# PT32S038x-Demo.net
KiCad netlist of a schematic drawn in EasyEDA Pro
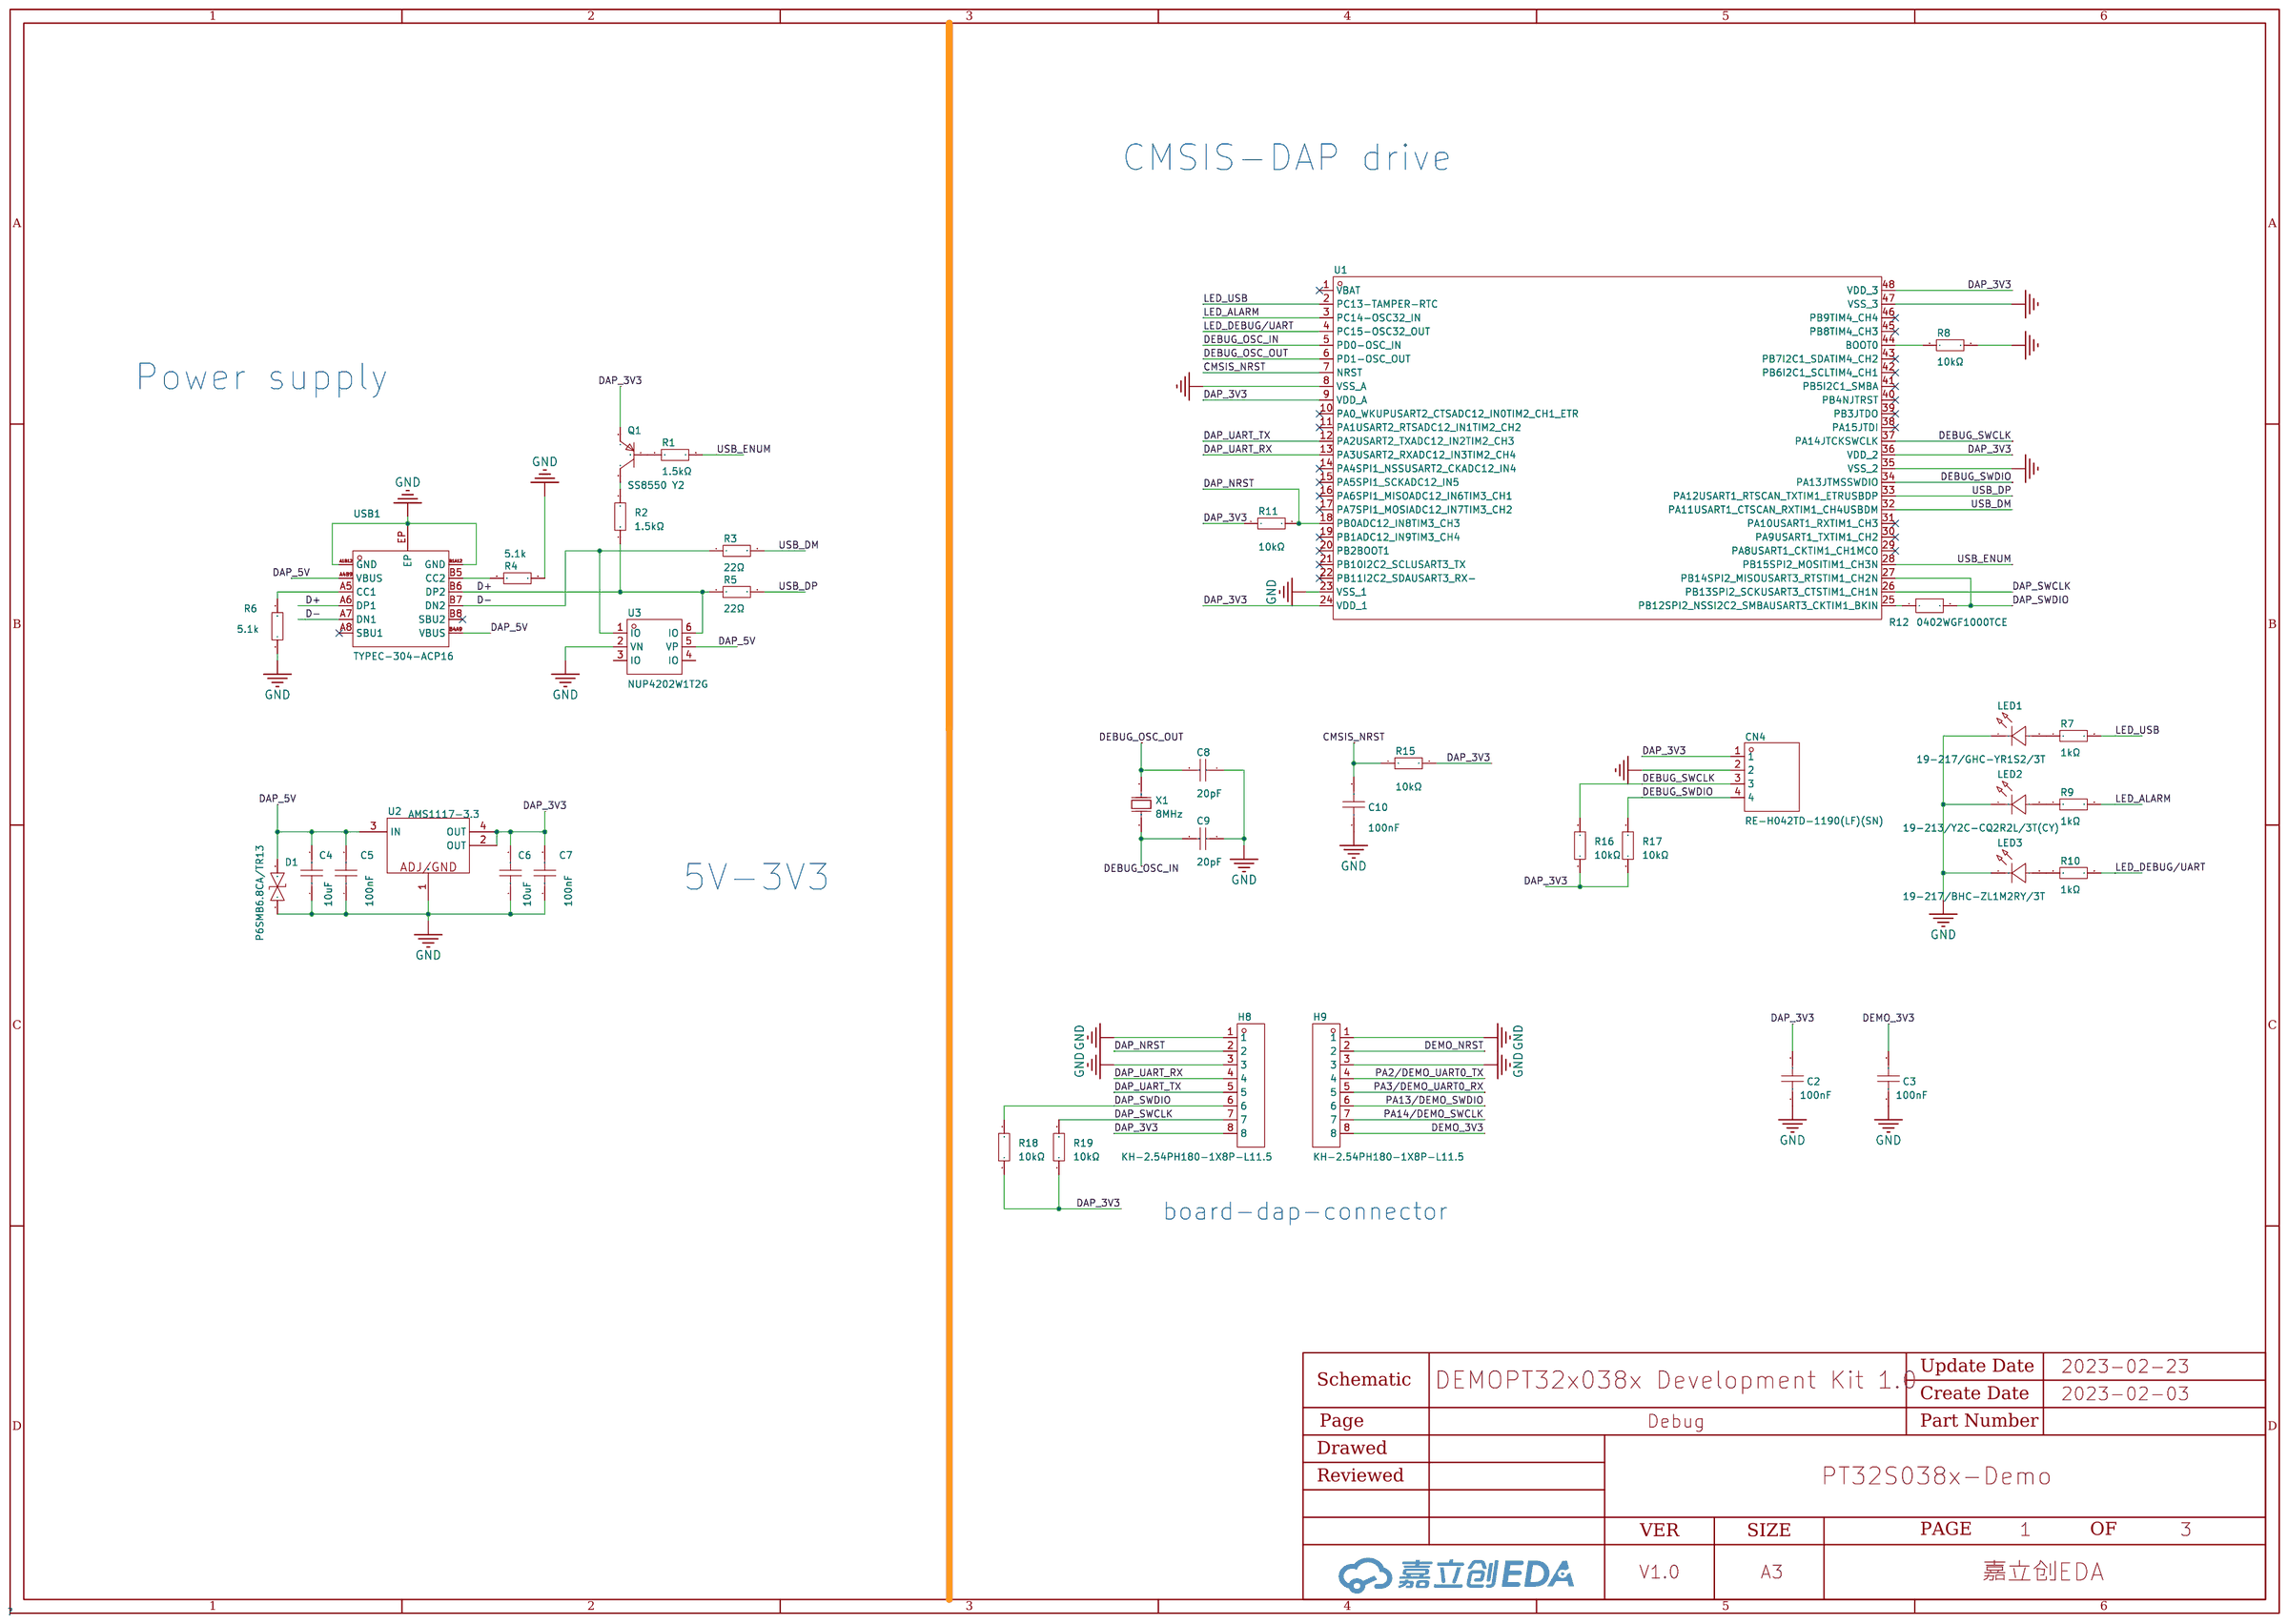
[diagram p0: Debug]
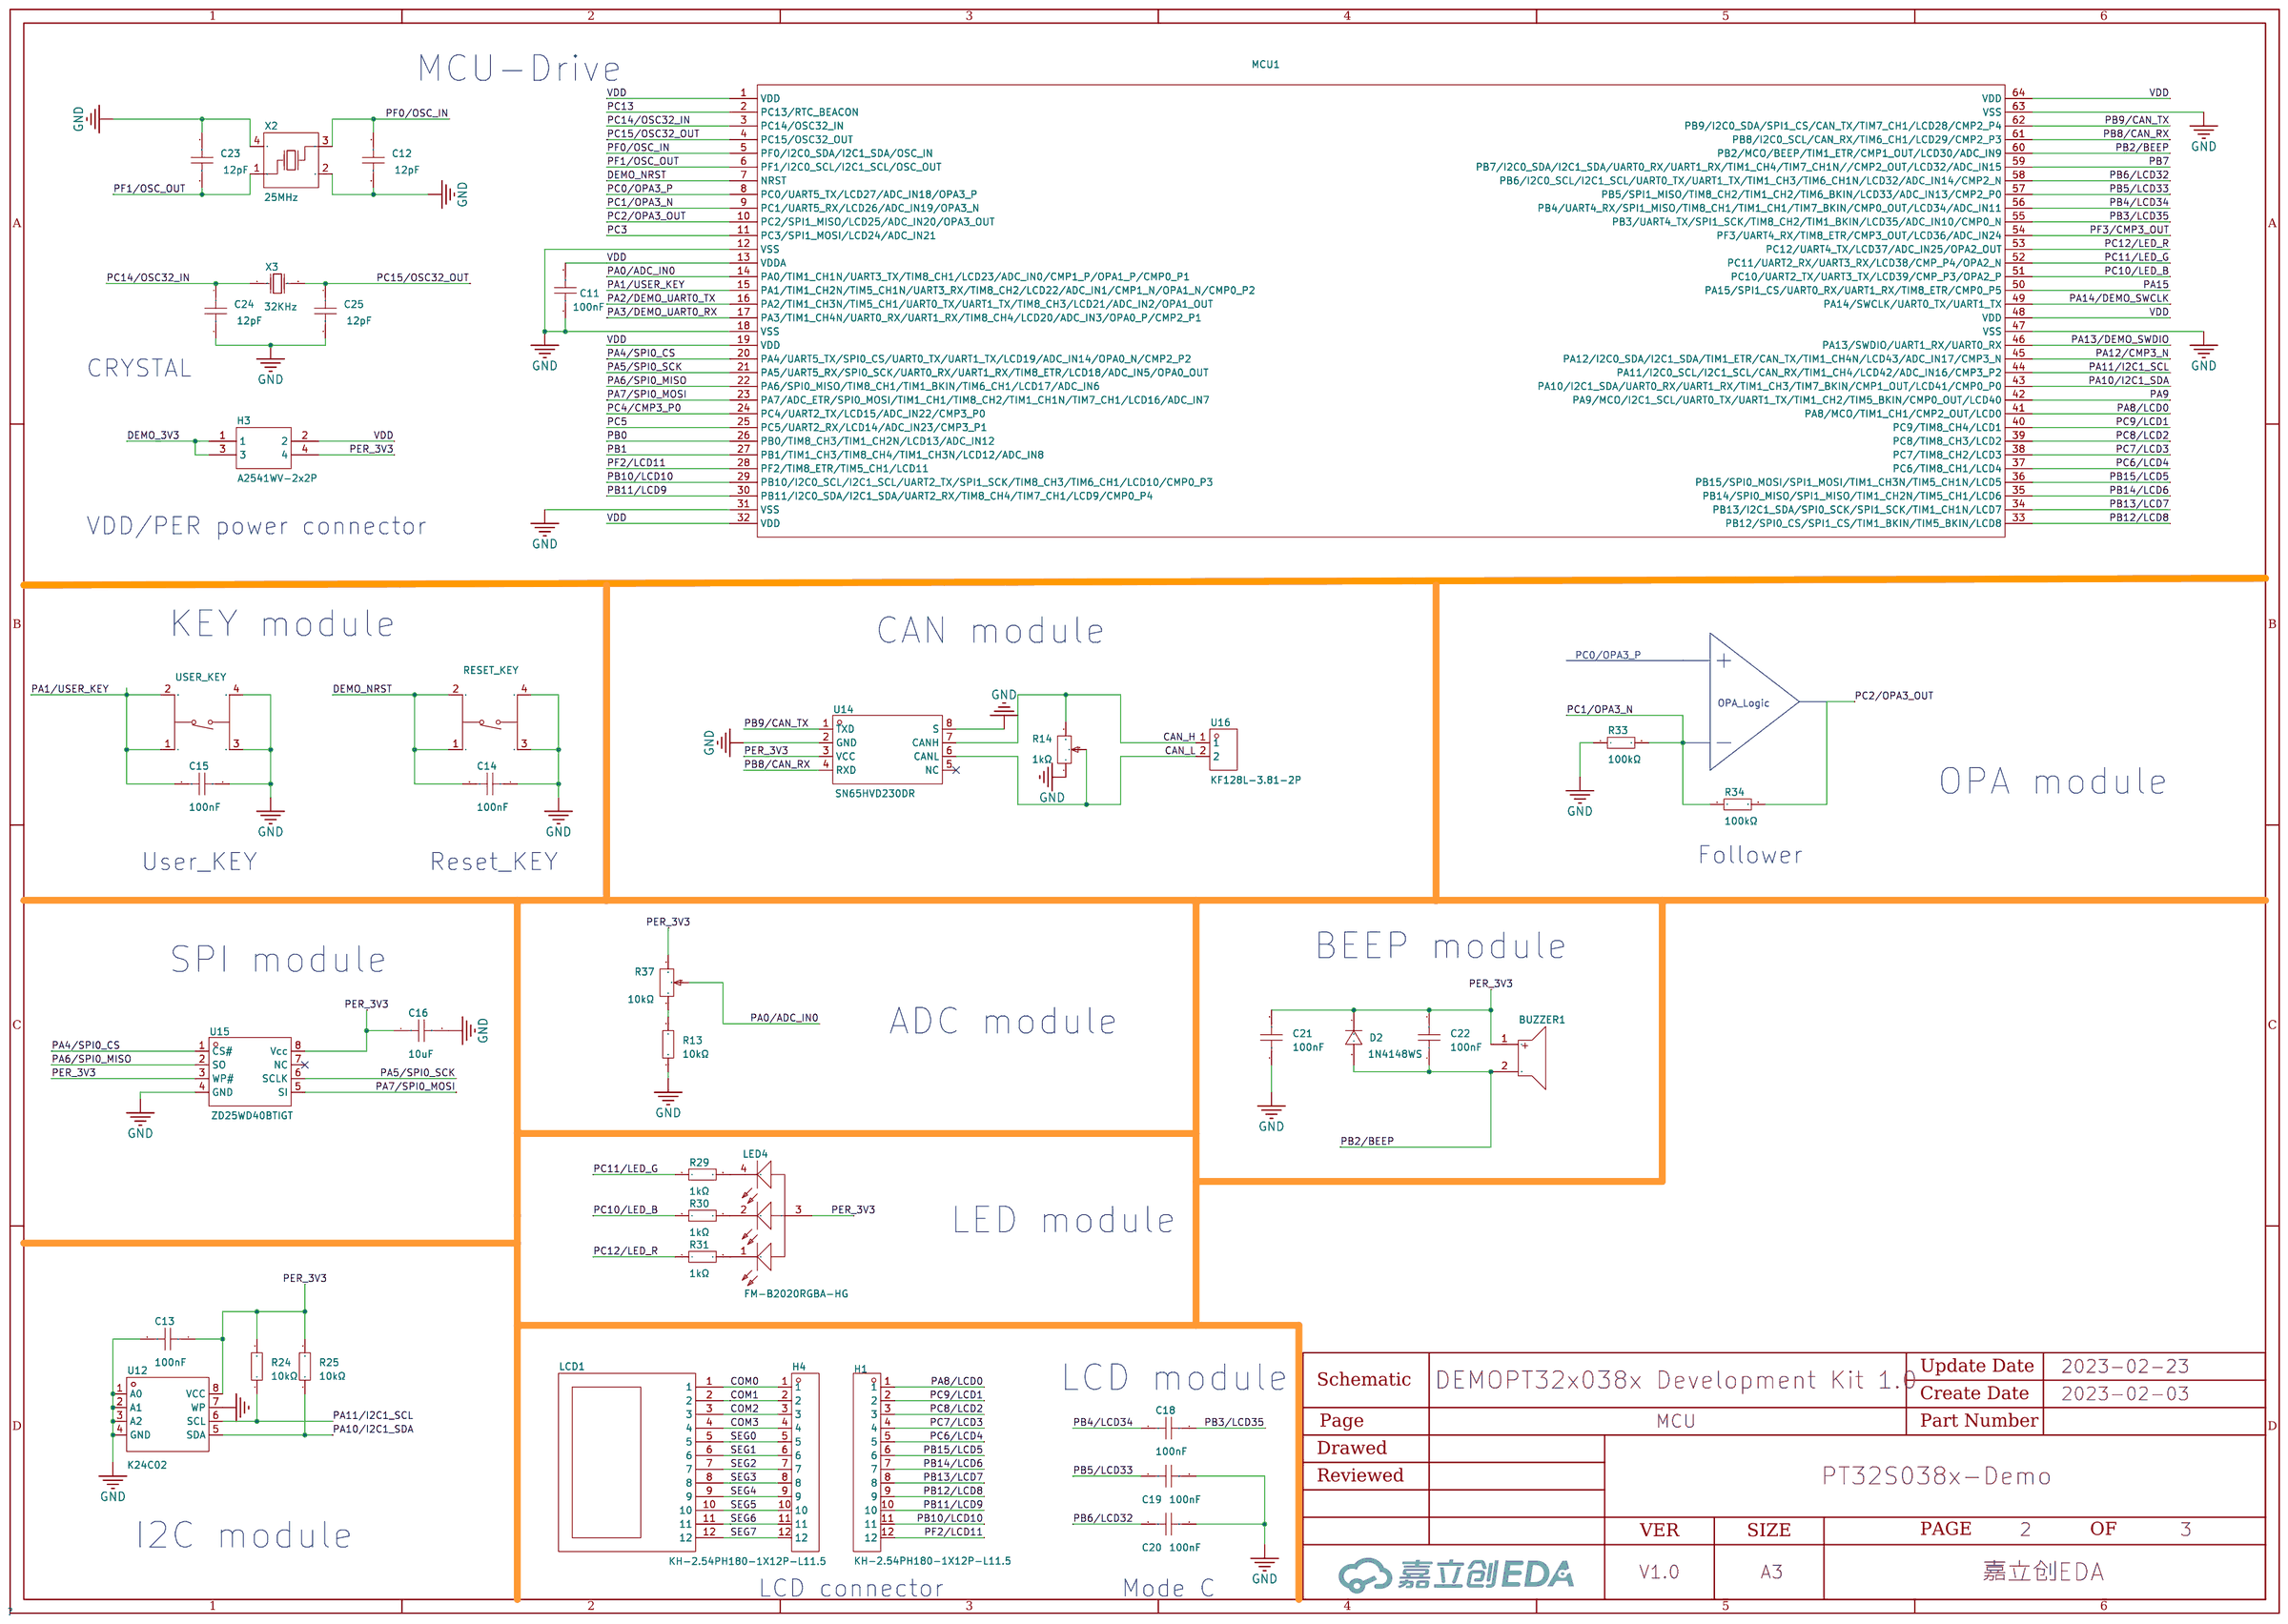
[diagram p1: MCU]
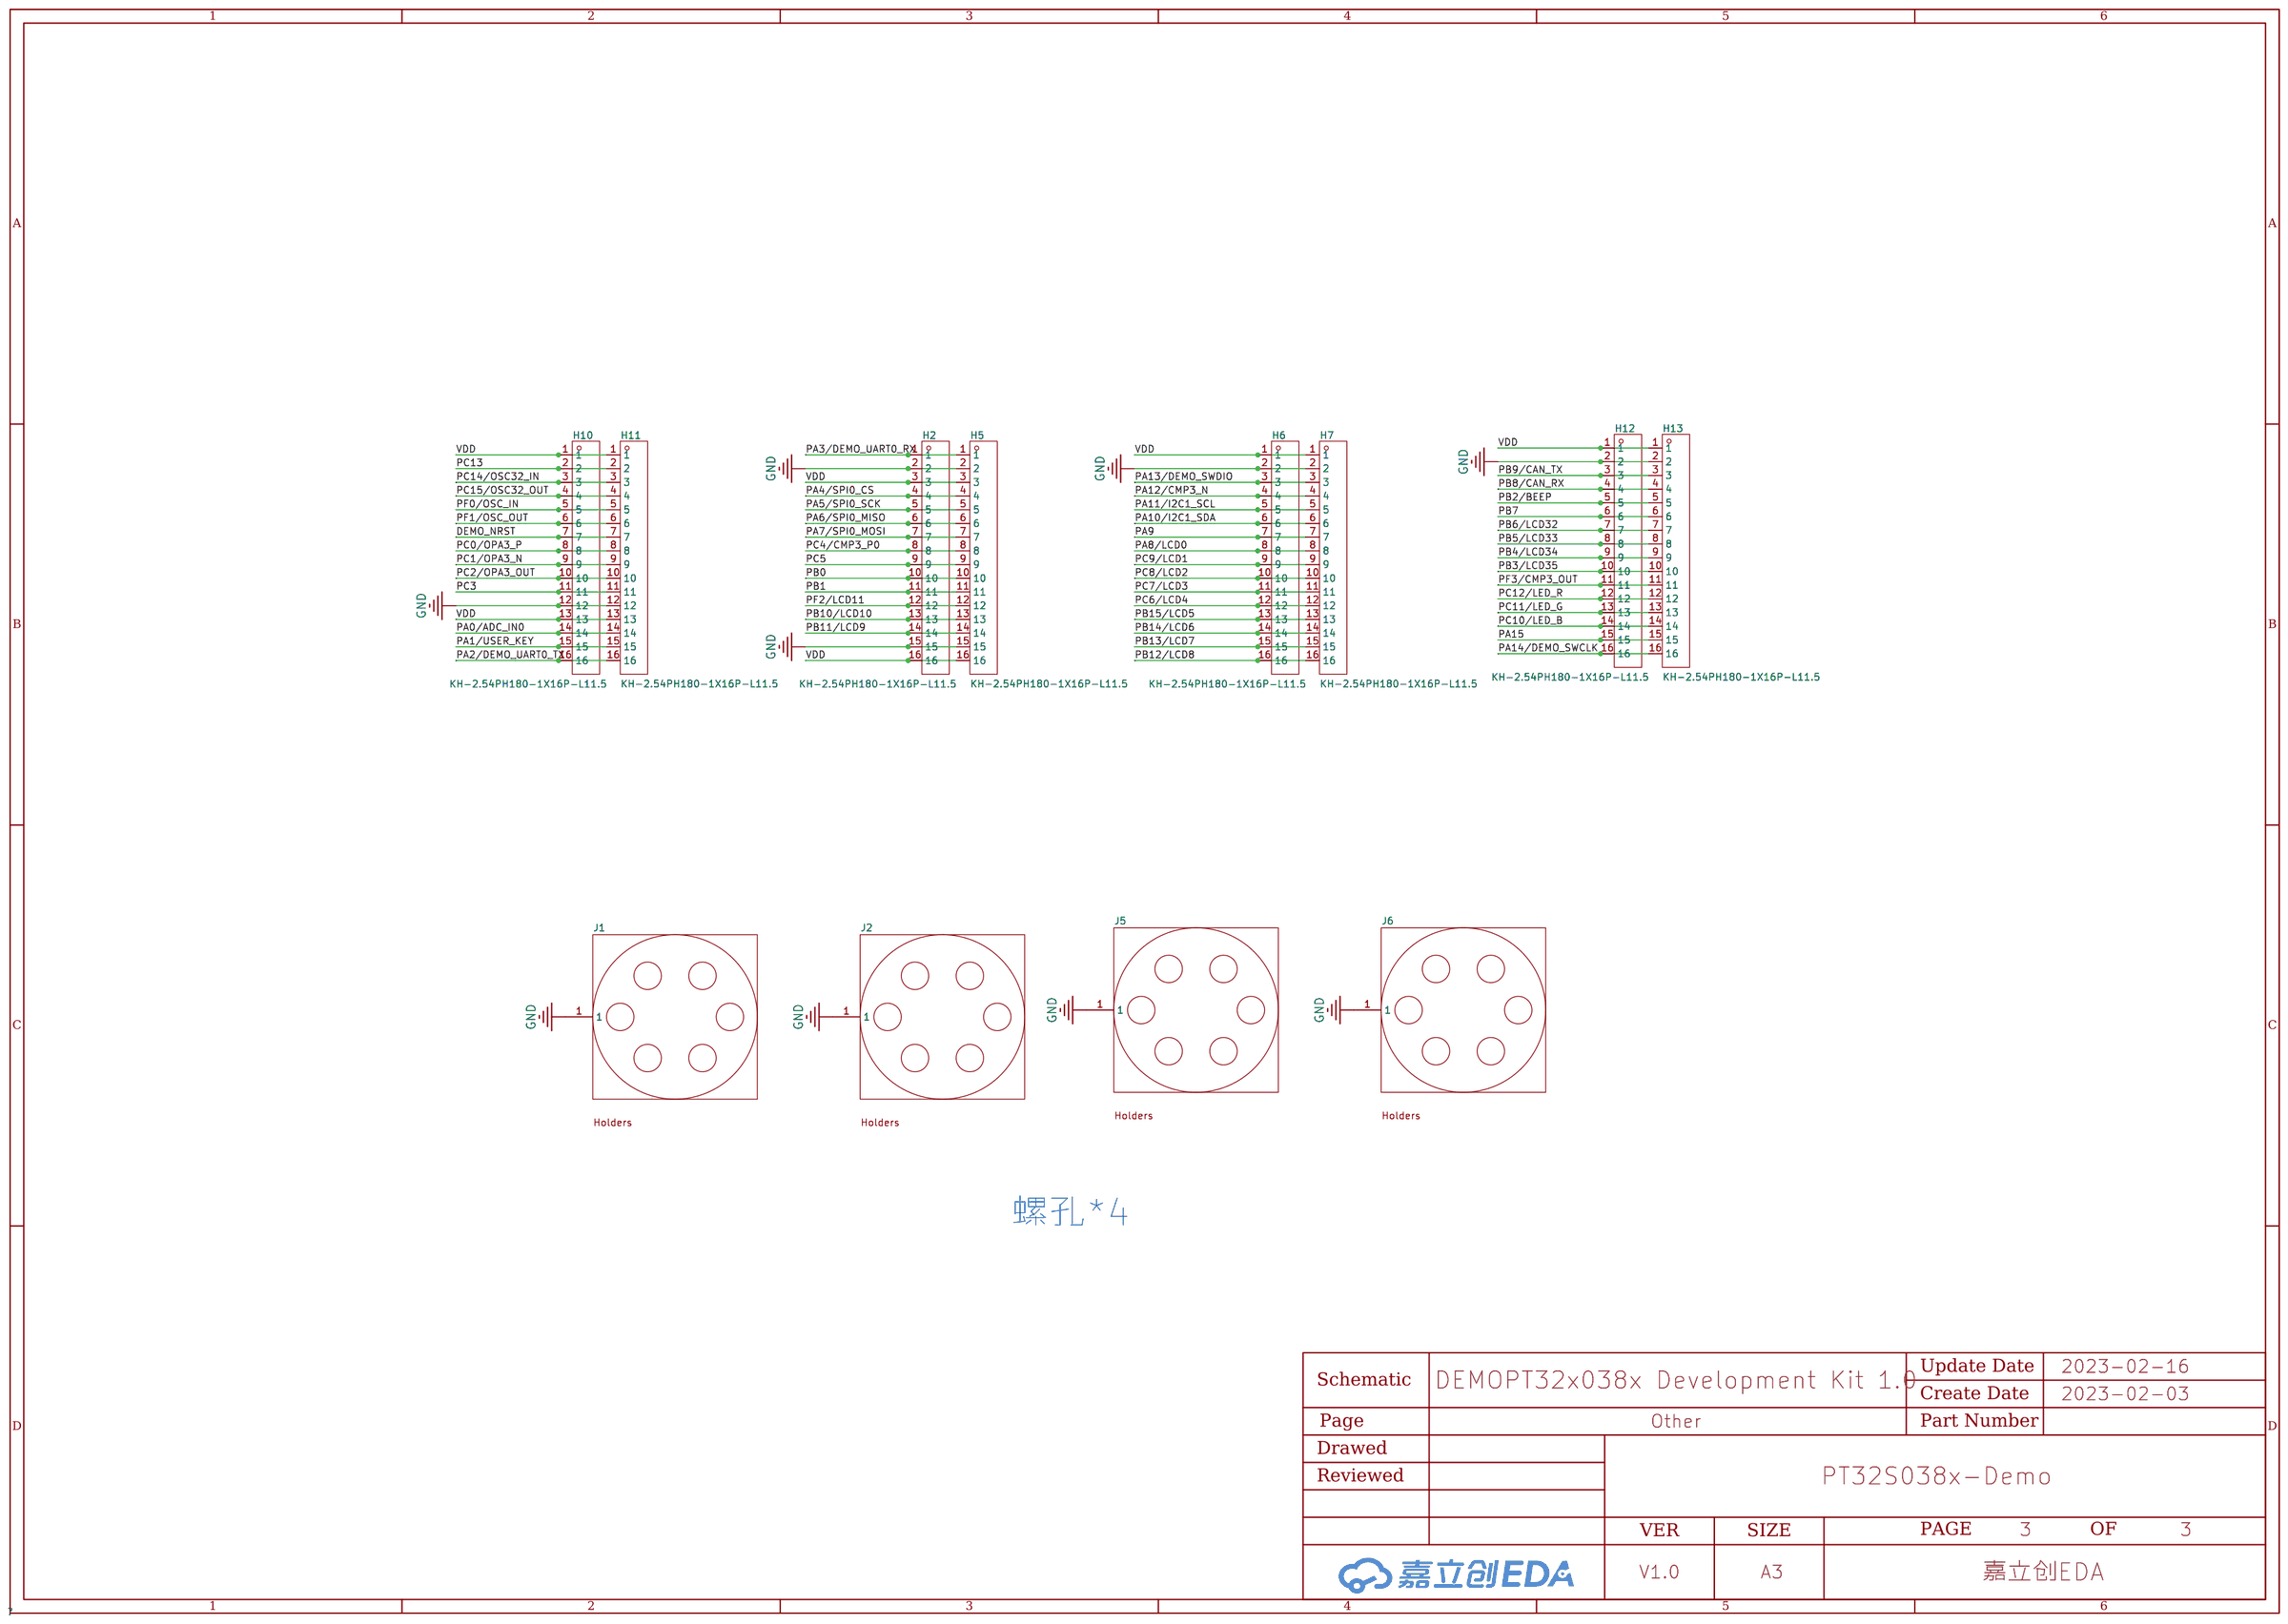
[diagram p2: Other]

(export (version "E")
  (design (tool "Eeschema 10.0.6"))
  (components
    (comp (ref "C2")
      (value "100nF")
      (footprint "easyedapro:C0603")
      (description "容值:100nF;精度:±10%;额定电压:50V;材质(温度系数):X7R;")
      (fields
        (field (name "Manufacturer Part") "CL05B104KB54PNC")
        (field (name "Manufacturer") "SAMSUNG(三星)")
      )
      (libsource (lib "easyedapro") (part "TCC0603X7R104K500CT"))
    )
    (comp (ref "C3")
      (value "100nF")
      (footprint "easyedapro:C0603")
      (description "容值:100nF;精度:±10%;额定电压:50V;材质(温度系数):X7R;")
      (fields
        (field (name "Manufacturer Part") "CL05B104KB54PNC")
        (field (name "Manufacturer") "SAMSUNG(三星)")
      )
      (libsource (lib "easyedapro") (part "TCC0603X7R104K500CT"))
    )
    (comp (ref "C4")
      (value "10uF")
      (footprint "easyedapro:C1210")
      (description "容值:10uF;精度:±10%;额定电压:50V;材质(温度系数):X7R;")
      (fields
        (field (name "Manufacturer Part") "CL31A106KBHNNNE")
        (field (name "Manufacturer") "SAMSUNG(三星)")
      )
      (libsource (lib "easyedapro") (part "C3225X7R1H106KT000E"))
    )
    (comp (ref "C5")
      (value "100nF")
      (footprint "easyedapro:C0603")
      (description "容值:100nF;精度:±10%;额定电压:50V;材质(温度系数):X7R;")
      (fields
        (field (name "Manufacturer Part") "CL05B104KB54PNC")
        (field (name "Manufacturer") "SAMSUNG(三星)")
      )
      (libsource (lib "easyedapro") (part "CC0603KRX7R9BB104"))
    )
    (comp (ref "C6")
      (value "10uF")
      (footprint "easyedapro:C1210")
      (description "容值:10uF;精度:±10%;额定电压:50V;材质(温度系数):X7R;")
      (fields
        (field (name "Manufacturer Part") "CL31A106KBHNNNE")
        (field (name "Manufacturer") "SAMSUNG(三星)")
      )
      (libsource (lib "easyedapro") (part "C3225X7R1H106KT000E"))
    )
    (comp (ref "C7")
      (value "100nF")
      (footprint "easyedapro:C0603")
      (description "容值:100nF;精度:±10%;额定电压:50V;材质(温度系数):X7R;")
      (fields
        (field (name "Manufacturer Part") "CL05B104KB54PNC")
        (field (name "Manufacturer") "SAMSUNG(三星)")
      )
      (libsource (lib "easyedapro") (part "CC0603KRX7R9BB104"))
    )
    (comp (ref "C8")
      (value "20pF")
      (footprint "easyedapro:C0603")
      (description "容值:20pF;精度:±5%;额定电压:50V;材质(温度系数):C0G;")
      (fields (field (name "Manufacturer Part") "0402CG200J500NT") (field (name "Manufacturer") "FH(风华)"))
      (libsource (lib "easyedapro") (part "GRM1885C1H200JA01D"))
    )
    (comp (ref "C9")
      (value "20pF")
      (footprint "easyedapro:C0603")
      (description "容值:20pF;精度:±5%;额定电压:50V;材质(温度系数):C0G;")
      (fields (field (name "Manufacturer Part") "0402CG200J500NT") (field (name "Manufacturer") "FH(风华)"))
      (libsource (lib "easyedapro") (part "GRM1885C1H200JA01D"))
    )
    (comp (ref "C10")
      (value "100nF")
      (footprint "easyedapro:C0603")
      (description "容值:100nF;精度:±10%;额定电压:50V;材质(温度系数):X7R;")
      (fields
        (field (name "Manufacturer Part") "CL05B104KB54PNC")
        (field (name "Manufacturer") "SAMSUNG(三星)")
      )
      (libsource (lib "easyedapro") (part "CC0603KRX7R9BB104"))
    )
    (comp (ref "CN4")
      (value "RE-H042TD-1190(LF)(SN)")
      (footprint "easyedapro:HDR-TH_4P-P2.54-V_RE-H042TD-1190")
      (fields (field (name "Manufacturer") "JST"))
      (libsource (lib "easyedapro") (part "RE-H042TD-1190 (LF)(SN)"))
    )
    (comp (ref "D1")
      (value "P6SMB6.8CA/TR13")
      (footprint "easyedapro:SMB_L4.6-W3.6-LS5.3-BI")
      (description "极性:双向;反向截止电压(Vrwm):5.8V;击穿电压(最小值):6.45V;峰值脉冲电流(Ipp)@10/1000s:58.1A;最大钳位电压:10.5V;")
      (fields (field (name "Manufacturer") "Brightking(君耀电子)"))
      (libsource (lib "easyedapro") (part "P6SMB6.8CA-C78395"))
    )
    (comp (ref "H8")
      (value "KH-2.54PH180-1X8P-L11.5")
      (footprint "easyedapro:HDR-TH_8P-P2.54-V-M")
      (fields (field (name "Manufacturer") "kinghelm(金航标)"))
      (libsource (lib "easyedapro") (part "KH-2.54PH180-1X8P-L11.5"))
    )
    (comp (ref "H9")
      (value "KH-2.54PH180-1X8P-L11.5")
      (footprint "easyedapro:HDR-TH_8P-P2.54-V-M")
      (fields (field (name "Manufacturer") "kinghelm(金航标)"))
      (libsource (lib "easyedapro") (part "KH-2.54PH180-1X8P-L11.5"))
    )
    (comp (ref "LED1")
      (value "19-217/GHC-YR1S2/3T")
      (footprint "easyedapro:LED0402-RD_GREEN")
      (fields (field (name "Manufacturer") "EVERLIGHT(亿光)"))
      (libsource (lib "easyedapro") (part "RF-GN0402TS-CF-B"))
    )
    (comp (ref "LED2")
      (value "19-213/Y2C-CQ2R2L/3T(CY)")
      (footprint "easyedapro:LED0402-RD_RED")
      (fields (field (name "Manufacturer") "EVERLIGHT(亿光)"))
      (libsource (lib "easyedapro") (part "RF-RU0402TS-BC-B1"))
    )
    (comp (ref "LED3")
      (value "19-217/BHC-ZL1M2RY/3T")
      (footprint "easyedapro:LED0402-RD_GREEN")
      (description "照明颜色:蓝色;主波长/色坐标:465~475nm;")
      (fields (field (name "Manufacturer") "EVERLIGHT(亿光)"))
      (libsource (lib "easyedapro") (part "RF-GN0402TS-CF-B"))
    )
    (comp (ref "Q1")
      (value "SS8550 Y2")
      (footprint "easyedapro:SOT-23-3_L2.9-W1.3-P1.90-LS2.4-BR")
      (fields (field (name "Manufacturer") "CJ(江苏长电/长晶)"))
      (libsource (lib "easyedapro") (part "SS8550_C8542"))
    )
    (comp (ref "R1")
      (value "1.5kΩ")
      (footprint "easyedapro:R0603")
      (description "阻值:1.5kΩ;精度:±1%;功率:1/16W;温度系数:±100ppm/℃;最大工作电压:50V;工作温度范围:-55℃~+155℃;")
      (fields
        (field (name "Manufacturer Part") "0402WGF1501TCE")
        (field (name "Manufacturer") "UNI-ROYAL(厚声)")
      )
      (libsource (lib "easyedapro") (part "0603WAF1501T5E"))
    )
    (comp (ref "R2")
      (value "1.5kΩ")
      (footprint "easyedapro:R0603")
      (description "阻值:1.5kΩ;精度:±1%;功率:1/16W;温度系数:±100ppm/℃;最大工作电压:50V;工作温度范围:-55℃~+155℃;")
      (fields
        (field (name "Manufacturer Part") "0402WGF1501TCE")
        (field (name "Manufacturer") "UNI-ROYAL(厚声)")
      )
      (libsource (lib "easyedapro") (part "0603WAF1501T5E"))
    )
    (comp (ref "R3")
      (value "22Ω")
      (footprint "easyedapro:R0402")
      (fields (field (name "Manufacturer") "UNI-ROYAL(厚声)"))
      (libsource (lib "easyedapro") (part "0402WGF220JTCE"))
    )
    (comp (ref "R4")
      (value "5.1kΩ")
      (footprint "easyedapro:R0603")
      (description "电阻类型:厚膜电阻;阻值:5.1kΩ;精度:±5%;功率:62.5mW;温度系数:±200ppm/℃;工作温度范围:-55℃~+155℃;")
      (fields (field (name "Manufacturer Part") "5.1k") (field (name "Manufacturer") "UNI-ROYAL(厚声)"))
      (libsource (lib "easyedapro") (part "RMC1/16-512JTP"))
    )
    (comp (ref "R5")
      (value "22Ω")
      (footprint "easyedapro:R0402")
      (fields (field (name "Manufacturer") "UNI-ROYAL(厚声)"))
      (libsource (lib "easyedapro") (part "0402WGF220JTCE"))
    )
    (comp (ref "R6")
      (value "5.1kΩ")
      (footprint "easyedapro:R0603")
      (description "电阻类型:厚膜电阻;阻值:5.1kΩ;精度:±5%;功率:62.5mW;温度系数:±200ppm/℃;工作温度范围:-55℃~+155℃;")
      (fields (field (name "Manufacturer Part") "5.1k") (field (name "Manufacturer") "UNI-ROYAL(厚声)"))
      (libsource (lib "easyedapro") (part "RMC1/16-512JTP"))
    )
    (comp (ref "R7")
      (value "1kΩ")
      (footprint "easyedapro:R0402")
      (description "电阻类型:厚膜电阻;阻值:1kΩ;精度:±1%;功率:62.5mW;温度系数:±100ppm/°C;最大工作电压:50V;工作温度范围:-55°C~+155°C;")
      (fields
        (field (name "Manufacturer Part") "0402WGF1001TCE")
        (field (name "Manufacturer") "UNI-ROYAL(厚声)")
      )
      (libsource (lib "easyedapro") (part "RC0402FR-071KL"))
    )
    (comp (ref "R8")
      (value "10kΩ")
      (footprint "easyedapro:R0603")
      (description "电阻类型:厚膜电阻;阻值:10kΩ;精度:±1%;功率:62.5mW;温度系数:±100ppm/℃;最大工作电压:50V;工作温度范围:-55℃~+155℃;")
      (fields
        (field (name "Manufacturer Part") "0402WGF1002TCE")
        (field (name "Manufacturer") "UNI-ROYAL(厚声)")
      )
      (libsource (lib "easyedapro") (part "RC0603JR-0710KL"))
    )
    (comp (ref "R9")
      (value "1kΩ")
      (footprint "easyedapro:R0402")
      (description "电阻类型:厚膜电阻;阻值:1kΩ;精度:±1%;功率:62.5mW;温度系数:±100ppm/°C;最大工作电压:50V;工作温度范围:-55°C~+155°C;")
      (fields
        (field (name "Manufacturer Part") "0402WGF1001TCE")
        (field (name "Manufacturer") "UNI-ROYAL(厚声)")
      )
      (libsource (lib "easyedapro") (part "RC0402FR-071KL"))
    )
    (comp (ref "R10")
      (value "1kΩ")
      (footprint "easyedapro:R0402")
      (description "电阻类型:厚膜电阻;阻值:1kΩ;精度:±1%;功率:62.5mW;温度系数:±100ppm/°C;最大工作电压:50V;工作温度范围:-55°C~+155°C;")
      (fields
        (field (name "Manufacturer Part") "0402WGF1001TCE")
        (field (name "Manufacturer") "UNI-ROYAL(厚声)")
      )
      (libsource (lib "easyedapro") (part "RC0402FR-071KL"))
    )
    (comp (ref "R11")
      (value "10kΩ")
      (footprint "easyedapro:R0603")
      (description "电阻类型:厚膜电阻;阻值:10kΩ;精度:±1%;功率:62.5mW;温度系数:±100ppm/℃;最大工作电压:50V;工作温度范围:-55℃~+155℃;")
      (fields
        (field (name "Manufacturer Part") "0402WGF1002TCE")
        (field (name "Manufacturer") "UNI-ROYAL(厚声)")
      )
      (libsource (lib "easyedapro") (part "RC0603JR-0710KL"))
    )
    (comp (ref "R12")
      (value "100Ω")
      (footprint "easyedapro:R0603")
      (description "电阻类型:厚膜电阻;阻值:100Ω;精度:±1%;功率:62.5mW;温度系数:±100ppm/℃;最大工作电压:50V;工作温度范围:-55℃~+155℃;")
      (fields
        (field (name "Manufacturer Part") "0402WGF1000TCE")
        (field (name "Manufacturer") "UNI-ROYAL(厚声)")
      )
      (libsource (lib "easyedapro") (part "0603 ±5% 100Ω"))
    )
    (comp (ref "R15")
      (value "10kΩ")
      (footprint "easyedapro:R0603")
      (description "电阻类型:厚膜电阻;阻值:10kΩ;精度:±1%;功率:62.5mW;温度系数:±100ppm/℃;最大工作电压:50V;工作温度范围:-55℃~+155℃;")
      (fields
        (field (name "Manufacturer Part") "0402WGF1002TCE")
        (field (name "Manufacturer") "UNI-ROYAL(厚声)")
      )
      (libsource (lib "easyedapro") (part "RC0603JR-0710KL"))
    )
    (comp (ref "R16")
      (value "10kΩ")
      (footprint "easyedapro:R0603")
      (description "电阻类型:厚膜电阻;阻值:10kΩ;精度:±1%;功率:62.5mW;温度系数:±100ppm/℃;最大工作电压:50V;工作温度范围:-55℃~+155℃;")
      (fields
        (field (name "Manufacturer Part") "0402WGF1002TCE")
        (field (name "Manufacturer") "UNI-ROYAL(厚声)")
      )
      (libsource (lib "easyedapro") (part "RC0603JR-0710KL"))
    )
    (comp (ref "R17")
      (value "10kΩ")
      (footprint "easyedapro:R0603")
      (description "电阻类型:厚膜电阻;阻值:10kΩ;精度:±1%;功率:62.5mW;温度系数:±100ppm/℃;最大工作电压:50V;工作温度范围:-55℃~+155℃;")
      (fields
        (field (name "Manufacturer Part") "0402WGF1002TCE")
        (field (name "Manufacturer") "UNI-ROYAL(厚声)")
      )
      (libsource (lib "easyedapro") (part "RC0603JR-0710KL"))
    )
    (comp (ref "R18")
      (value "10kΩ")
      (footprint "easyedapro:R0603")
      (description "电阻类型:厚膜电阻;阻值:10kΩ;精度:±1%;功率:62.5mW;温度系数:±100ppm/℃;最大工作电压:50V;工作温度范围:-55℃~+155℃;")
      (fields
        (field (name "Manufacturer Part") "0402WGF1002TCE")
        (field (name "Manufacturer") "UNI-ROYAL(厚声)")
      )
      (libsource (lib "easyedapro") (part "RC0603JR-0710KL"))
    )
    (comp (ref "R19")
      (value "10kΩ")
      (footprint "easyedapro:R0603")
      (description "电阻类型:厚膜电阻;阻值:10kΩ;精度:±1%;功率:62.5mW;温度系数:±100ppm/℃;最大工作电压:50V;工作温度范围:-55℃~+155℃;")
      (fields
        (field (name "Manufacturer Part") "0402WGF1002TCE")
        (field (name "Manufacturer") "UNI-ROYAL(厚声)")
      )
      (libsource (lib "easyedapro") (part "RC0603JR-0710KL"))
    )
    (comp (ref "U1")
      (value "STM32F103CBT6")
      (footprint "easyedapro:LQFP-48_L7.0-W7.0-P0.50-LS9.0-BL")
      (description "主频（MAX):72MHz;工作电压:2V ~ 3.6V;")
      (fields (field (name "Manufacturer") "ST(意法半导体)"))
      (libsource (lib "easyedapro") (part "STM32F103CBT6"))
    )
    (comp (ref "U2")
      (value "AMS1117-3.3")
      (footprint "easyedapro:SOT-223-3_L6.4-W3.5-P2.30-LS7.0-BR")
      (fields (field (name "Manufacturer") "AMS"))
      (libsource (lib "easyedapro") (part "AMS1117-3.3_C2992570"))
    )
    (comp (ref "U3")
      (value "NUP4202W1T2G")
      (footprint "easyedapro:SOT-363_L2.0-W1.3-P0.65-LS2.1-BR")
      (fields (field (name "Manufacturer") "onsemi(安森美)"))
      (libsource (lib "easyedapro") (part "NUP4202W1T2G"))
    )
    (comp (ref "USB1")
      (value "TYPEC-304-ACP16")
      (footprint "easyedapro:USB-C-SMD_TYPE-C-16P-1")
      (description "连接器类型:-;标准:-;公母:-;触点数量:-;端口数量:-;安装方式:-;额定电流 - 电源:-;触头材质:-;触头镀层:-;工作温度范围:-;")
      (fields (field (name "Manufacturer") "XUNPU(讯普)"))
      (libsource (lib "easyedapro") (part "TYPEC-304-ACP16"))
    )
    (comp (ref "X1")
      (value "8MHz")
      (footprint "easyedapro:CRYSTAL-SMD_L5.0-W3.2")
      (description "晶振类型:贴片无源晶振;频率:8MHz;频率公差:±10ppm;频率稳定度:±50ppm;负载电容:20pF;工作温度:-40℃~+85℃;")
      (fields (field (name "Manufacturer Part") "X50328MSB2GI") (field (name "Manufacturer") "YXC(扬兴晶振)"))
      (libsource (lib "easyedapro") (part "ECS-80-8-30Q-VY-TR"))
    )
    (comp (ref "BUZZER1")
      (value "2700Hz")
      (footprint "easyedapro:BUZ-TH_BD9.0-P4.00-D0.6-FD")
      (description "驱动方式:无源(外部驱动);构造类型:电磁式;额定电压:3V;工作电压:2V~5V;频率:2700Hz;声压(SPL):85dB@3V,10cm;直径(φD):9mm;高度:5.7mm;")
      (fields (field (name "Manufacturer Part") "FS9042-03") (field (name "Manufacturer") "FUET(福声科技)"))
      (libsource (lib "easyedapro") (part "QMB-09B-03"))
    )
    (comp (ref "C11")
      (value "100nF")
      (footprint "easyedapro:C0603")
      (description "容值:100nF;精度:±10%;额定电压:50V;材质(温度系数):X7R;")
      (fields
        (field (name "Manufacturer Part") "CL05B104KB54PNC")
        (field (name "Manufacturer") "SAMSUNG(三星)")
      )
      (libsource (lib "easyedapro") (part "TCC0603X7R104K500CT"))
    )
    (comp (ref "C12")
      (value "12pF")
      (footprint "easyedapro:C0402")
      (description "容值:12pF;精度:±5%;额定电压:50V;材质(温度系数):C0G;")
      (fields (field (name "Manufacturer Part") "0402CG120J500NT") (field (name "Manufacturer") "FH(风华)"))
      (libsource (lib "easyedapro") (part "GJM1555C1H120GB01D"))
    )
    (comp (ref "C13")
      (value "100nF")
      (footprint "easyedapro:C0603")
      (description "容值:100nF;精度:±10%;额定电压:50V;材质(温度系数):X7R;")
      (fields
        (field (name "Manufacturer Part") "CL05B104KB54PNC")
        (field (name "Manufacturer") "SAMSUNG(三星)")
      )
      (libsource (lib "easyedapro") (part "TCC0603X7R104K500CT"))
    )
    (comp (ref "C14")
      (value "100nF")
      (footprint "easyedapro:C0603")
      (description "容值:100nF;精度:±10%;额定电压:50V;材质(温度系数):X7R;")
      (fields
        (field (name "Manufacturer Part") "CL05B104KB54PNC")
        (field (name "Manufacturer") "SAMSUNG(三星)")
      )
      (libsource (lib "easyedapro") (part "TCC0603X7R104K500CT"))
    )
    (comp (ref "C15")
      (value "100nF")
      (footprint "easyedapro:C0603")
      (description "容值:100nF;精度:±10%;额定电压:50V;材质(温度系数):X7R;")
      (fields
        (field (name "Manufacturer Part") "CL05B104KB54PNC")
        (field (name "Manufacturer") "SAMSUNG(三星)")
      )
      (libsource (lib "easyedapro") (part "TCC0603X7R104K500CT"))
    )
    (comp (ref "C16")
      (value "10uF")
      (footprint "easyedapro:C0402")
      (description "容值:10uF;精度:±20%;额定电压:10V;材质(温度系数):X5R;")
      (fields
        (field (name "Manufacturer Part") "CL05A106MQ5NUNC")
        (field (name "Manufacturer") "SAMSUNG(三星)")
      )
      (libsource (lib "easyedapro") (part "CL05A106MP5NUNC_C315248"))
    )
    (comp (ref "C18")
      (value "100nF")
      (footprint "easyedapro:C0603")
      (description "容值:100nF;精度:±10%;额定电压:50V;材质(温度系数):X7R;")
      (fields
        (field (name "Manufacturer Part") "CL05B104KB54PNC")
        (field (name "Manufacturer") "SAMSUNG(三星)")
      )
      (libsource (lib "easyedapro") (part "TCC0603X7R104K500CT"))
    )
    (comp (ref "C19")
      (value "100nF")
      (footprint "easyedapro:C0603")
      (description "容值:100nF;精度:±10%;额定电压:50V;材质(温度系数):X7R;")
      (fields
        (field (name "Manufacturer Part") "CL05B104KB54PNC")
        (field (name "Manufacturer") "SAMSUNG(三星)")
      )
      (libsource (lib "easyedapro") (part "TCC0603X7R104K500CT"))
    )
    (comp (ref "C20")
      (value "100nF")
      (footprint "easyedapro:C0603")
      (description "容值:100nF;精度:±10%;额定电压:50V;材质(温度系数):X7R;")
      (fields
        (field (name "Manufacturer Part") "CL05B104KB54PNC")
        (field (name "Manufacturer") "SAMSUNG(三星)")
      )
      (libsource (lib "easyedapro") (part "TCC0603X7R104K500CT"))
    )
    (comp (ref "C21")
      (value "100nF")
      (footprint "easyedapro:C0603")
      (description "容值:100nF;精度:±10%;额定电压:50V;材质(温度系数):X7R;")
      (fields
        (field (name "Manufacturer Part") "CL05B104KB54PNC")
        (field (name "Manufacturer") "SAMSUNG(三星)")
      )
      (libsource (lib "easyedapro") (part "TCC0603X7R104K500CT"))
    )
    (comp (ref "C22")
      (value "100nF")
      (footprint "easyedapro:C0603")
      (description "容值:100nF;精度:±10%;额定电压:50V;材质(温度系数):X7R;")
      (fields
        (field (name "Manufacturer Part") "CL05B104KB54PNC")
        (field (name "Manufacturer") "SAMSUNG(三星)")
      )
      (libsource (lib "easyedapro") (part "TCC0603X7R104K500CT"))
    )
    (comp (ref "C23")
      (value "12pF")
      (footprint "easyedapro:C0402")
      (description "容值:12pF;精度:±5%;额定电压:50V;材质(温度系数):C0G;")
      (fields (field (name "Manufacturer Part") "0402CG120J500NT") (field (name "Manufacturer") "FH(风华)"))
      (libsource (lib "easyedapro") (part "GJM1555C1H120GB01D"))
    )
    (comp (ref "C24")
      (value "12pF")
      (footprint "easyedapro:C0402")
      (description "容值:12pF;精度:±5%;额定电压:50V;材质(温度系数):C0G;")
      (fields (field (name "Manufacturer Part") "0402CG120J500NT") (field (name "Manufacturer") "FH(风华)"))
      (libsource (lib "easyedapro") (part "GJM1555C1H120GB01D"))
    )
    (comp (ref "C25")
      (value "12pF")
      (footprint "easyedapro:C0402")
      (description "容值:12pF;精度:±5%;额定电压:50V;材质(温度系数):C0G;")
      (fields (field (name "Manufacturer Part") "0402CG120J500NT") (field (name "Manufacturer") "FH(风华)"))
      (libsource (lib "easyedapro") (part "GJM1555C1H120GB01D"))
    )
    (comp (ref "D2")
      (value "1N4148WS")
      (footprint "easyedapro:SOD-323_L1.8-W1.3-LS2.5-RD")
      (fields (field (name "Manufacturer") "CJ(江苏长电/长晶)"))
      (libsource (lib "easyedapro") (part "IN4148WS"))
    )
    (comp (ref "H1")
      (value "KH-2.54PH180-1X12P-L11.5")
      (footprint "easyedapro:HDR-TH_12P-P2.54-V-M")
      (fields (field (name "Manufacturer") "kinghelm(金航标)"))
      (libsource (lib "easyedapro") (part "KH-2.54PH180-1X12P-L11.5"))
    )
    (comp (ref "H3")
      (value "A2541WV-2x2P")
      (footprint "easyedapro:HDR-TH_4P-P2.54-V-R2-C2-S2.54_A2541WV-2X2P")
      (fields (field (name "Manufacturer") "CJT(长江连接器)"))
      (libsource (lib "easyedapro") (part "A2541WV-2X2P"))
    )
    (comp (ref "H4")
      (value "KH-2.54PH180-1X12P-L11.5")
      (footprint "easyedapro:HDR-TH_12P-P2.54-V-M")
      (fields (field (name "Manufacturer") "kinghelm(金航标)"))
      (libsource (lib "easyedapro") (part "KH-2.54PH180-1X12P-L11.5"))
    )
    (comp (ref "LCD1")
      (value "~")
      (footprint "easyedapro:LCD_12pin_4com_8seg")
      (description "LCD screen with 4COM and 8SEG")
      (libsource (lib "easyedapro") (part "LCD_12pin_4com_8seg"))
    )
    (comp (ref "LED4")
      (value "FM-B2020RGBA-HG")
      (footprint "easyedapro:LED-SMD_FM-B2020RGBA-HG")
      (description "发光颜色:RGB三色;")
      (fields (field (name "Manufacturer") "国星光电"))
      (libsource (lib "easyedapro") (part "FM-B2020RGBA-HG"))
    )
    (comp (ref "MCU1")
      (value "~")
      (description "PengPai-Microelectronics Micro control uint")
      (libsource (lib "easyedapro") (part "PT32S038x"))
    )
    (comp (ref "R13")
      (value "10kΩ")
      (footprint "easyedapro:R0603")
      (description "电阻类型:厚膜电阻;阻值:10kΩ;精度:±1%;功率:62.5mW;温度系数:±100ppm/℃;最大工作电压:50V;工作温度范围:-55℃~+155℃;")
      (fields
        (field (name "Manufacturer Part") "0402WGF1002TCE")
        (field (name "Manufacturer") "UNI-ROYAL(厚声)")
      )
      (libsource (lib "easyedapro") (part "RC0603JR-0710KL"))
    )
    (comp (ref "R14")
      (value "1kΩ")
      (footprint "easyedapro:RES-ADJ-TH_3362P")
      (description "阻值:1kΩ;精度:±10%;")
      (fields (field (name "Manufacturer Part") "3362P-1-102LF") (field (name "Manufacturer") "BOURNS"))
      (libsource (lib "easyedapro") (part "3362P-1-102LF"))
    )
    (comp (ref "R24")
      (value "10kΩ")
      (footprint "easyedapro:R0603")
      (description "电阻类型:厚膜电阻;阻值:10kΩ;精度:±1%;功率:62.5mW;温度系数:±100ppm/℃;最大工作电压:50V;工作温度范围:-55℃~+155℃;")
      (fields
        (field (name "Manufacturer Part") "0402WGF1002TCE")
        (field (name "Manufacturer") "UNI-ROYAL(厚声)")
      )
      (libsource (lib "easyedapro") (part "RC0603JR-0710KL"))
    )
    (comp (ref "R25")
      (value "10kΩ")
      (footprint "easyedapro:R0603")
      (description "电阻类型:厚膜电阻;阻值:10kΩ;精度:±1%;功率:62.5mW;温度系数:±100ppm/℃;最大工作电压:50V;工作温度范围:-55℃~+155℃;")
      (fields
        (field (name "Manufacturer Part") "0402WGF1002TCE")
        (field (name "Manufacturer") "UNI-ROYAL(厚声)")
      )
      (libsource (lib "easyedapro") (part "RC0603JR-0710KL"))
    )
    (comp (ref "R29")
      (value "1kΩ")
      (footprint "easyedapro:R0402")
      (description "电阻类型:厚膜电阻;阻值:1kΩ;精度:±1%;功率:62.5mW;温度系数:±100ppm/°C;最大工作电压:50V;工作温度范围:-55°C~+155°C;")
      (fields
        (field (name "Manufacturer Part") "0402WGF1001TCE")
        (field (name "Manufacturer") "UNI-ROYAL(厚声)")
      )
      (libsource (lib "easyedapro") (part "RC0402FR-071KL"))
    )
    (comp (ref "R30")
      (value "1kΩ")
      (footprint "easyedapro:R0402")
      (description "电阻类型:厚膜电阻;阻值:1kΩ;精度:±1%;功率:62.5mW;温度系数:±100ppm/°C;最大工作电压:50V;工作温度范围:-55°C~+155°C;")
      (fields
        (field (name "Manufacturer Part") "0402WGF1001TCE")
        (field (name "Manufacturer") "UNI-ROYAL(厚声)")
      )
      (libsource (lib "easyedapro") (part "RC0402FR-071KL"))
    )
    (comp (ref "R31")
      (value "1kΩ")
      (footprint "easyedapro:R0402")
      (description "电阻类型:厚膜电阻;阻值:1kΩ;精度:±1%;功率:62.5mW;温度系数:±100ppm/°C;最大工作电压:50V;工作温度范围:-55°C~+155°C;")
      (fields
        (field (name "Manufacturer Part") "0402WGF1001TCE")
        (field (name "Manufacturer") "UNI-ROYAL(厚声)")
      )
      (libsource (lib "easyedapro") (part "RC0402FR-071KL"))
    )
    (comp (ref "R33")
      (value "100kΩ")
      (footprint "easyedapro:R0402")
      (description "电阻类型:厚膜电阻;阻值:100kΩ;精度:±1%;功率:62.5mW;温度系数:±100ppm/°C;最大工作电压:50V;工作温度范围:-55°C~+155°C;")
      (fields
        (field (name "Manufacturer Part") "0402WGF1003TCE")
        (field (name "Manufacturer") "UNI-ROYAL(厚声)")
      )
      (libsource (lib "easyedapro") (part "0402WGF1003TCE"))
    )
    (comp (ref "R34")
      (value "100kΩ")
      (footprint "easyedapro:R0402")
      (description "电阻类型:厚膜电阻;阻值:100kΩ;精度:±1%;功率:62.5mW;温度系数:±100ppm/°C;最大工作电压:50V;工作温度范围:-55°C~+155°C;")
      (fields
        (field (name "Manufacturer Part") "0402WGF1003TCE")
        (field (name "Manufacturer") "UNI-ROYAL(厚声)")
      )
      (libsource (lib "easyedapro") (part "0402WGF1003TCE"))
    )
    (comp (ref "R37")
      (value "10kΩ")
      (footprint "easyedapro:RES-ADJ-TH_3362P")
      (description "阻值:10kΩ;精度:±10%;")
      (fields (field (name "Manufacturer Part") "3362P-1-103LF") (field (name "Manufacturer") "BOURNS"))
      (libsource (lib "easyedapro") (part "3362P-1-102LF"))
    )
    (comp (ref "RESET_KEY")
      (value "TS-1187A-B-A-B")
      (footprint "easyedapro:SW-SMD_4P-L5.1-W5.1-P3.70-LS6.5-TL-2")
      (description "触点电流:20mA;额定电压(DC):12V;电路结构:单刀单掷;安装方式:立贴;按钮形状:圆形按钮;带灯:-;开关长度:5.1mm;开关宽度:5.1mm;开关高度:0.3mm;")
      (fields (field (name "Manufacturer") "XKB Connectivity(中国星坤)"))
      (libsource (lib "easyedapro") (part "1TS001G-2500-1500"))
    )
    (comp (ref "U12")
      (value "K24C02")
      (footprint "easyedapro:SOIC-8_L4.9-W3.9-P1.27-LS6.0-BL")
      (description "2-Kbit(256 x 8bit)，I2C接口，工作电压：1.7V to 5.5V")
      (fields (field (name "Manufacturer") "华虹宏力"))
      (libsource (lib "easyedapro") (part "K24C02_C10510"))
    )
    (comp (ref "U14")
      (value "SN65HVD230DR")
      (footprint "easyedapro:SOIC-8_L4.9-W3.9-P1.27-LS6.0-BL")
      (description "类型:收发器;数据速率:5Mbps;电源电压(Vcc):4.5V~5.5V;")
      (fields (field (name "Manufacturer") "TI(德州仪器)"))
      (libsource (lib "easyedapro") (part "TJA1051T/1J"))
    )
    (comp (ref "U15")
      (value "ZD25WD40BTIGT")
      (footprint "easyedapro:SOIC-8_L4.9-W3.9-P1.27-LS6.0-BL")
      (description "SPI NOR Flash，4Mb，2.3-3.6V，SOP8-150，Tube")
      (fields (field (name "Manufacturer") "Zetta(澜智)"))
      (libsource (lib "easyedapro") (part "ZD25WD40BTIGT"))
    )
    (comp (ref "U16")
      (value "KF128L-3.81-2P")
      (footprint "easyedapro:CONN-TH_P3.81_KF128L-3.81-2P")
      (fields (field (name "Manufacturer") "KEFA(科发)"))
      (libsource (lib "easyedapro") (part "KF128L-3.81-2P"))
    )
    (comp (ref "USER_KEY")
      (value "TS-1187A-B-A-B")
      (footprint "easyedapro:SW-SMD_4P-L5.1-W5.1-P3.70-LS6.5-TL-2")
      (description "触点电流:20mA;额定电压(DC):12V;电路结构:单刀单掷;安装方式:立贴;按钮形状:圆形按钮;带灯:-;开关长度:5.1mm;开关宽度:5.1mm;开关高度:0.3mm;")
      (fields (field (name "Manufacturer") "XKB Connectivity(中国星坤)"))
      (libsource (lib "easyedapro") (part "1TS001G-2500-1500"))
    )
    (comp (ref "X2")
      (value "25MHz")
      (footprint "easyedapro:OSC-SMD_4P-L3.2-W2.5-BL")
      (description "晶振类型:贴片无源晶振;频率:25MHz;频率公差:±10ppm;频率稳定度:±30ppm;负载电容:12pF;工作温度:-40~+85;")
      (fields (field (name "Manufacturer Part") "X322525MOB4SI") (field (name "Manufacturer") "YXC(扬兴晶振)"))
      (libsource (lib "easyedapro") (part "X322525MOB4SI"))
    )
    (comp (ref "X3")
      (value "32KHz")
      (footprint "easyedapro:OSC-SMD_L3.2-W1.5")
      (description "晶振类型:-;频率:-;负载电容:-;工作温度:-;")
      (fields (field (name "Manufacturer Part") "DST310S 32.768KHz") (field (name "Manufacturer") "KDS(大真空)"))
      (libsource (lib "easyedapro") (part "DST310S 32.768KHz"))
    )
    (comp (ref "H2")
      (value "KH-2.54PH180-1X16P-L11.5")
      (footprint "easyedapro:HDR-TH_16P-P2.54-V-M")
      (fields (field (name "Manufacturer") "kinghelm(金航标)"))
      (libsource (lib "easyedapro") (part "KH-2.54PH180-1X16P-L11.5"))
    )
    (comp (ref "H5")
      (value "KH-2.54PH180-1X16P-L11.5")
      (footprint "easyedapro:HDR-TH_16P-P2.54-V-M")
      (fields (field (name "Manufacturer") "kinghelm(金航标)"))
      (libsource (lib "easyedapro") (part "KH-2.54PH180-1X16P-L11.5"))
    )
    (comp (ref "H6")
      (value "KH-2.54PH180-1X16P-L11.5")
      (footprint "easyedapro:HDR-TH_16P-P2.54-V-M")
      (fields (field (name "Manufacturer") "kinghelm(金航标)"))
      (libsource (lib "easyedapro") (part "KH-2.54PH180-1X16P-L11.5"))
    )
    (comp (ref "H7")
      (value "KH-2.54PH180-1X16P-L11.5")
      (footprint "easyedapro:HDR-TH_16P-P2.54-V-M")
      (fields (field (name "Manufacturer") "kinghelm(金航标)"))
      (libsource (lib "easyedapro") (part "KH-2.54PH180-1X16P-L11.5"))
    )
    (comp (ref "H10")
      (value "KH-2.54PH180-1X16P-L11.5")
      (footprint "easyedapro:HDR-TH_16P-P2.54-V-M")
      (fields (field (name "Manufacturer") "kinghelm(金航标)"))
      (libsource (lib "easyedapro") (part "KH-2.54PH180-1X16P-L11.5"))
    )
    (comp (ref "H11")
      (value "KH-2.54PH180-1X16P-L11.5")
      (footprint "easyedapro:HDR-TH_16P-P2.54-V-M")
      (fields (field (name "Manufacturer") "kinghelm(金航标)"))
      (libsource (lib "easyedapro") (part "KH-2.54PH180-1X16P-L11.5"))
    )
    (comp (ref "H12")
      (value "KH-2.54PH180-1X16P-L11.5")
      (footprint "easyedapro:HDR-TH_16P-P2.54-V-M")
      (fields (field (name "Manufacturer") "kinghelm(金航标)"))
      (libsource (lib "easyedapro") (part "KH-2.54PH180-1X16P-L11.5"))
    )
    (comp (ref "H13")
      (value "KH-2.54PH180-1X16P-L11.5")
      (footprint "easyedapro:HDR-TH_16P-P2.54-V-M")
      (fields (field (name "Manufacturer") "kinghelm(金航标)"))
      (libsource (lib "easyedapro") (part "KH-2.54PH180-1X16P-L11.5"))
    )
    (comp (ref "J1")
      (value "~")
      (footprint "easyedapro:DEMO板安装孔")
      (libsource (lib "easyedapro") (part "螺孔_3.1X6MM"))
    )
    (comp (ref "J2")
      (value "~")
      (footprint "easyedapro:DEMO板安装孔")
      (libsource (lib "easyedapro") (part "螺孔_3.1X6MM"))
    )
    (comp (ref "J5")
      (value "~")
      (footprint "easyedapro:DEMO板安装孔")
      (libsource (lib "easyedapro") (part "螺孔_3.1X6MM"))
    )
    (comp (ref "J6")
      (value "~")
      (footprint "easyedapro:DEMO板安装孔")
      (libsource (lib "easyedapro") (part "螺孔_3.1X6MM"))
    )
  )
  (nets
    (net (code "1") (name "CAN_H") (class "Default")
      (node (ref "R14") (pin "3") (pinfunction "3_3") (pintype "input"))
      (node (ref "U14") (pin "7") (pinfunction "CANH_7") (pintype "input"))
      (node (ref "U16") (pin "1") (pinfunction "1_1") (pintype "input"))
    )
    (net (code "2") (name "CAN_L") (class "Default")
      (node (ref "R14") (pin "2") (pinfunction "2_2") (pintype "input"))
      (node (ref "U14") (pin "6") (pinfunction "CANL_6") (pintype "input"))
      (node (ref "U16") (pin "2") (pinfunction "2_2") (pintype "input"))
    )
    (net (code "3") (name "CMSIS_NRST") (class "Default")
      (node (ref "C10") (pin "2") (pinfunction "2_2") (pintype "input"))
      (node (ref "R15") (pin "1") (pinfunction "1_1") (pintype "input"))
      (node (ref "U1") (pin "7") (pinfunction "NRST_7") (pintype "input"))
    )
    (net (code "4") (name "COM0") (class "Default")
      (node (ref "H4") (pin "1") (pinfunction "1_1") (pintype "input"))
      (node (ref "LCD1") (pin "1") (pinfunction "1_1") (pintype "input"))
    )
    (net (code "5") (name "COM1") (class "Default")
      (node (ref "H4") (pin "2") (pinfunction "2_2") (pintype "input"))
      (node (ref "LCD1") (pin "2") (pinfunction "2_2") (pintype "input"))
    )
    (net (code "6") (name "COM2") (class "Default")
      (node (ref "H4") (pin "3") (pinfunction "3_3") (pintype "input"))
      (node (ref "LCD1") (pin "3") (pinfunction "3_3") (pintype "input"))
    )
    (net (code "7") (name "COM3") (class "Default")
      (node (ref "H4") (pin "4") (pinfunction "4_4") (pintype "input"))
      (node (ref "LCD1") (pin "4") (pinfunction "4_4") (pintype "input"))
    )
    (net (code "8") (name "D+") (class "Default")
      (node (ref "R2") (pin "1") (pinfunction "1_1") (pintype "input"))
      (node (ref "R5") (pin "1") (pinfunction "1_1") (pintype "input"))
      (node (ref "U3") (pin "6") (pinfunction "IO_6") (pintype "input"))
      (node (ref "USB1") (pin "A6") (pinfunction "DP1_A6") (pintype "input"))
      (node (ref "USB1") (pin "B6") (pinfunction "DP2_B6") (pintype "input"))
    )
    (net (code "9") (name "D-") (class "Default")
      (node (ref "R3") (pin "1") (pinfunction "1_1") (pintype "input"))
      (node (ref "U3") (pin "1") (pinfunction "IO_1") (pintype "input"))
      (node (ref "USB1") (pin "A7") (pinfunction "DN1_A7") (pintype "input"))
      (node (ref "USB1") (pin "B7") (pinfunction "DN2_B7") (pintype "input"))
    )
    (net (code "10") (name "DAP_3V3") (class "Default")
      (node (ref "C2") (pin "2") (pinfunction "2_2") (pintype "input"))
      (node (ref "C6") (pin "2") (pinfunction "2_2") (pintype "input"))
      (node (ref "C7") (pin "2") (pinfunction "2_2") (pintype "input"))
      (node (ref "CN4") (pin "1") (pinfunction "1_1") (pintype "input"))
      (node (ref "H8") (pin "8") (pinfunction "8_8") (pintype "input"))
      (node (ref "Q1") (pin "2") (pinfunction "E_2") (pintype "input"))
      (node (ref "R11") (pin "1") (pinfunction "1_1") (pintype "input"))
      (node (ref "R15") (pin "2") (pinfunction "2_2") (pintype "input"))
      (node (ref "R16") (pin "1") (pinfunction "1_1") (pintype "input"))
      (node (ref "R17") (pin "1") (pinfunction "1_1") (pintype "input"))
      (node (ref "R18") (pin "1") (pinfunction "1_1") (pintype "input"))
      (node (ref "R19") (pin "1") (pinfunction "1_1") (pintype "input"))
      (node (ref "U1") (pin "24") (pinfunction "VDD_1_24") (pintype "input"))
      (node (ref "U1") (pin "36") (pinfunction "VDD_2_36") (pintype "input"))
      (node (ref "U1") (pin "48") (pinfunction "VDD_3_48") (pintype "input"))
      (node (ref "U1") (pin "9") (pinfunction "VDD_A_9") (pintype "input"))
      (node (ref "U2") (pin "2") (pinfunction "OUT_2") (pintype "input"))
      (node (ref "U2") (pin "4") (pinfunction "OUT_4") (pintype "input"))
    )
    (net (code "11") (name "DAP_5V") (class "Default")
      (node (ref "C4") (pin "2") (pinfunction "2_2") (pintype "input"))
      (node (ref "C5") (pin "2") (pinfunction "2_2") (pintype "input"))
      (node (ref "D1") (pin "2") (pinfunction "2_2") (pintype "input"))
      (node (ref "U2") (pin "3") (pinfunction "IN_3") (pintype "input"))
      (node (ref "U3") (pin "5") (pinfunction "VP_5") (pintype "input"))
      (node (ref "USB1") (pin "A4B9") (pinfunction "VBUS_A4B9") (pintype "input"))
      (node (ref "USB1") (pin "B4A9") (pinfunction "VBUS_B4A9") (pintype "input"))
    )
    (net (code "12") (name "DAP_NRST") (class "Default")
      (node (ref "H8") (pin "2") (pinfunction "2_2") (pintype "input"))
      (node (ref "R11") (pin "2") (pinfunction "2_2") (pintype "input"))
      (node (ref "U1") (pin "18") (pinfunction "PB0ADC12_IN8TIM3_CH3_18") (pintype "input"))
    )
    (net (code "13") (name "DAP_SWCLK") (class "Default")
      (node (ref "H8") (pin "7") (pinfunction "7_7") (pintype "input"))
      (node (ref "R19") (pin "2") (pinfunction "2_2") (pintype "input"))
      (node (ref "U1") (pin "26") (pinfunction "PB13SPI2_SCKUSART3_CTSTIM1_CH1N_26") (pintype "input"))
    )
    (net (code "14") (name "DAP_SWDIO") (class "Default")
      (node (ref "H8") (pin "6") (pinfunction "6_6") (pintype "input"))
      (node (ref "R12") (pin "2") (pinfunction "2_2") (pintype "input"))
      (node (ref "R18") (pin "2") (pinfunction "2_2") (pintype "input"))
      (node (ref "U1") (pin "27") (pinfunction "PB14SPI2_MISOUSART3_RTSTIM1_CH2N_27") (pintype "input"))
    )
    (net (code "15") (name "DAP_UART_RX") (class "Default")
      (node (ref "H8") (pin "4") (pinfunction "4_4") (pintype "input"))
      (node (ref "U1") (pin "13") (pinfunction "PA3USART2_RXADC12_IN3TIM2_CH4_13") (pintype "input"))
    )
    (net (code "16") (name "DAP_UART_TX") (class "Default")
      (node (ref "H8") (pin "5") (pinfunction "5_5") (pintype "input"))
      (node (ref "U1") (pin "12") (pinfunction "PA2USART2_TXADC12_IN2TIM2_CH3_12") (pintype "input"))
    )
    (net (code "17") (name "DEBUG_OSC_IN") (class "Default")
      (node (ref "C9") (pin "2") (pinfunction "2_2") (pintype "input"))
      (node (ref "U1") (pin "5") (pinfunction "PD0-OSC_IN_5") (pintype "input"))
      (node (ref "X1") (pin "1") (pinfunction "In/Out_1") (pintype "input"))
    )
    (net (code "18") (name "DEBUG_OSC_OUT") (class "Default")
      (node (ref "C8") (pin "2") (pinfunction "2_2") (pintype "input"))
      (node (ref "U1") (pin "6") (pinfunction "PD1-OSC_OUT_6") (pintype "input"))
      (node (ref "X1") (pin "2") (pinfunction "Out/In_2") (pintype "input"))
    )
    (net (code "19") (name "DEBUG_SWCLK") (class "Default")
      (node (ref "CN4") (pin "3") (pinfunction "3_3") (pintype "input"))
      (node (ref "R16") (pin "2") (pinfunction "2_2") (pintype "input"))
      (node (ref "U1") (pin "37") (pinfunction "PA14JTCKSWCLK_37") (pintype "input"))
    )
    (net (code "20") (name "DEBUG_SWDIO") (class "Default")
      (node (ref "CN4") (pin "4") (pinfunction "4_4") (pintype "input"))
      (node (ref "R17") (pin "2") (pinfunction "2_2") (pintype "input"))
      (node (ref "U1") (pin "34") (pinfunction "PA13JTMSSWDIO_34") (pintype "input"))
    )
    (net (code "21") (name "DEMO_3V3") (class "Default")
      (node (ref "C3") (pin "2") (pinfunction "2_2") (pintype "input"))
      (node (ref "H3") (pin "1") (pinfunction "1_1") (pintype "input"))
      (node (ref "H3") (pin "3") (pinfunction "3_3") (pintype "input"))
      (node (ref "H9") (pin "8") (pinfunction "8_8") (pintype "input"))
    )
    (net (code "22") (name "DEMO_NRST") (class "Default")
      (node (ref "C14") (pin "2") (pinfunction "2_2") (pintype "input"))
      (node (ref "H10") (pin "7") (pinfunction "7_7") (pintype "input"))
      (node (ref "H11") (pin "7") (pinfunction "7_7") (pintype "input"))
      (node (ref "H9") (pin "2") (pinfunction "2_2") (pintype "input"))
      (node (ref "MCU1") (pin "7") (pinfunction "NRST_7") (pintype "input"))
      (node (ref "RESET_KEY") (pin "1") (pinfunction "A_1") (pintype "input"))
      (node (ref "RESET_KEY") (pin "2") (pinfunction "B_2") (pintype "input"))
    )
    (net (code "23") (name "GND") (class "Default")
      (node (ref "C10") (pin "1") (pinfunction "1_1") (pintype "input"))
      (node (ref "C11") (pin "1") (pinfunction "1_1") (pintype "input"))
      (node (ref "C12") (pin "2") (pinfunction "2_2") (pintype "input"))
      (node (ref "C13") (pin "2") (pinfunction "2_2") (pintype "input"))
      (node (ref "C14") (pin "1") (pinfunction "1_1") (pintype "input"))
      (node (ref "C15") (pin "1") (pinfunction "1_1") (pintype "input"))
      (node (ref "C16") (pin "2") (pinfunction "2_2") (pintype "input"))
      (node (ref "C19") (pin "2") (pinfunction "2_2") (pintype "input"))
      (node (ref "C2") (pin "1") (pinfunction "1_1") (pintype "input"))
      (node (ref "C20") (pin "2") (pinfunction "2_2") (pintype "input"))
      (node (ref "C21") (pin "1") (pinfunction "1_1") (pintype "input"))
      (node (ref "C23") (pin "1") (pinfunction "1_1") (pintype "input"))
      (node (ref "C24") (pin "2") (pinfunction "2_2") (pintype "input"))
      (node (ref "C25") (pin "2") (pinfunction "2_2") (pintype "input"))
      (node (ref "C3") (pin "1") (pinfunction "1_1") (pintype "input"))
      (node (ref "C4") (pin "1") (pinfunction "1_1") (pintype "input"))
      (node (ref "C5") (pin "1") (pinfunction "1_1") (pintype "input"))
      (node (ref "C6") (pin "1") (pinfunction "1_1") (pintype "input"))
      (node (ref "C7") (pin "1") (pinfunction "1_1") (pintype "input"))
      (node (ref "C8") (pin "1") (pinfunction "1_1") (pintype "input"))
      (node (ref "C9") (pin "1") (pinfunction "1_1") (pintype "input"))
      (node (ref "CN4") (pin "2") (pinfunction "2_2") (pintype "input"))
      (node (ref "D1") (pin "1") (pinfunction "1_1") (pintype "input"))
      (node (ref "H10") (pin "12") (pinfunction "12_12") (pintype "input"))
      (node (ref "H11") (pin "12") (pinfunction "12_12") (pintype "input"))
      (node (ref "H12") (pin "2") (pinfunction "2_2") (pintype "input"))
      (node (ref "H13") (pin "2") (pinfunction "2_2") (pintype "input"))
      (node (ref "H2") (pin "15") (pinfunction "15_15") (pintype "input"))
      (node (ref "H2") (pin "2") (pinfunction "2_2") (pintype "input"))
      (node (ref "H5") (pin "15") (pinfunction "15_15") (pintype "input"))
      (node (ref "H5") (pin "2") (pinfunction "2_2") (pintype "input"))
      (node (ref "H6") (pin "2") (pinfunction "2_2") (pintype "input"))
      (node (ref "H7") (pin "2") (pinfunction "2_2") (pintype "input"))
      (node (ref "H8") (pin "1") (pinfunction "1_1") (pintype "input"))
      (node (ref "H8") (pin "3") (pinfunction "3_3") (pintype "input"))
      (node (ref "H9") (pin "1") (pinfunction "1_1") (pintype "input"))
      (node (ref "H9") (pin "3") (pinfunction "3_3") (pintype "input"))
      (node (ref "J1") (pin "1") (pinfunction "1_1") (pintype "input"))
      (node (ref "J2") (pin "1") (pinfunction "1_1") (pintype "input"))
      (node (ref "J5") (pin "1") (pinfunction "1_1") (pintype "input"))
      (node (ref "J6") (pin "1") (pinfunction "1_1") (pintype "input"))
      (node (ref "LED1") (pin "1") (pinfunction "K_1") (pintype "input"))
      (node (ref "LED2") (pin "1") (pinfunction "K_1") (pintype "input"))
      (node (ref "LED3") (pin "1") (pinfunction "K_1") (pintype "input"))
      (node (ref "MCU1") (pin "12") (pinfunction "VSS_12") (pintype "input"))
      (node (ref "MCU1") (pin "18") (pinfunction "VSS_18") (pintype "input"))
      (node (ref "MCU1") (pin "31") (pinfunction "VSS_31") (pintype "input"))
      (node (ref "MCU1") (pin "47") (pinfunction "VSS_47") (pintype "input"))
      (node (ref "MCU1") (pin "63") (pinfunction "VSS_63") (pintype "input"))
      (node (ref "R13") (pin "1") (pinfunction "1_1") (pintype "input"))
      (node (ref "R14") (pin "1") (pinfunction "1_1") (pintype "input"))
      (node (ref "R33") (pin "1") (pinfunction "1_1") (pintype "input"))
      (node (ref "R4") (pin "2") (pinfunction "2_2") (pintype "input"))
      (node (ref "R6") (pin "1") (pinfunction "1_1") (pintype "input"))
      (node (ref "R8") (pin "2") (pinfunction "2_2") (pintype "input"))
      (node (ref "RESET_KEY") (pin "3") (pinfunction "C_3") (pintype "input"))
      (node (ref "RESET_KEY") (pin "4") (pinfunction "D_4") (pintype "input"))
      (node (ref "U1") (pin "23") (pinfunction "VSS_1_23") (pintype "input"))
      (node (ref "U1") (pin "35") (pinfunction "VSS_2_35") (pintype "input"))
      (node (ref "U1") (pin "47") (pinfunction "VSS_3_47") (pintype "input"))
      (node (ref "U1") (pin "8") (pinfunction "VSS_A_8") (pintype "input"))
      (node (ref "U12") (pin "1") (pinfunction "A0_1") (pintype "input"))
      (node (ref "U12") (pin "2") (pinfunction "A1_2") (pintype "input"))
      (node (ref "U12") (pin "3") (pinfunction "A2_3") (pintype "input"))
      (node (ref "U12") (pin "4") (pinfunction "GND_4") (pintype "input"))
      (node (ref "U12") (pin "7") (pinfunction "WP_7") (pintype "input"))
      (node (ref "U14") (pin "2") (pinfunction "GND_2") (pintype "input"))
      (node (ref "U14") (pin "8") (pinfunction "S_8") (pintype "input"))
      (node (ref "U15") (pin "4") (pinfunction "GND_4") (pintype "input"))
      (node (ref "U2") (pin "1") (pinfunction "ADJ/GND_1") (pintype "input"))
      (node (ref "U3") (pin "2") (pinfunction "VN_2") (pintype "input"))
      (node (ref "USB1") (pin "A1B12") (pinfunction "GND_A1B12") (pintype "input"))
      (node (ref "USB1") (pin "B1A12") (pinfunction "GND_B1A12") (pintype "input"))
      (node (ref "USB1") (pin "EP") (pinfunction "EP_EP") (pintype "input"))
      (node (ref "USER_KEY") (pin "3") (pinfunction "C_3") (pintype "input"))
      (node (ref "USER_KEY") (pin "4") (pinfunction "D_4") (pintype "input"))
      (node (ref "X2") (pin "2") (pinfunction "GND_2") (pintype "input"))
      (node (ref "X2") (pin "4") (pinfunction "GND_4") (pintype "input"))
    )
    (net (code "24") (name "LED_ALARM") (class "Default")
      (node (ref "R9") (pin "2") (pinfunction "2_2") (pintype "input"))
      (node (ref "U1") (pin "3") (pinfunction "PC14-OSC32_IN_3") (pintype "input"))
    )
    (net (code "25") (name "LED_DEBUG{slash}UART") (class "Default")
      (node (ref "R10") (pin "2") (pinfunction "2_2") (pintype "input"))
      (node (ref "U1") (pin "4") (pinfunction "PC15-OSC32_OUT_4") (pintype "input"))
    )
    (net (code "26") (name "LED_USB") (class "Default")
      (node (ref "R7") (pin "2") (pinfunction "2_2") (pintype "input"))
      (node (ref "U1") (pin "2") (pinfunction "PC13-TAMPER-RTC_2") (pintype "input"))
    )
    (net (code "27") (name "Net-(LED1-A)") (class "Default")
      (node (ref "LED1") (pin "2") (pinfunction "A_2") (pintype "input"))
      (node (ref "R7") (pin "1") (pinfunction "1_1") (pintype "input"))
    )
    (net (code "28") (name "Net-(LED2-A)") (class "Default")
      (node (ref "LED2") (pin "2") (pinfunction "A_2") (pintype "input"))
      (node (ref "R9") (pin "1") (pinfunction "1_1") (pintype "input"))
    )
    (net (code "29") (name "Net-(LED3-A)") (class "Default")
      (node (ref "LED3") (pin "2") (pinfunction "A_2") (pintype "input"))
      (node (ref "R10") (pin "1") (pinfunction "1_1") (pintype "input"))
    )
    (net (code "30") (name "Net-(LED4-K-Pad1)") (class "Default")
      (node (ref "LED4") (pin "1") (pinfunction "K_1") (pintype "input"))
      (node (ref "R31") (pin "2") (pinfunction "2_2") (pintype "input"))
    )
    (net (code "31") (name "Net-(LED4-K-Pad2)") (class "Default")
      (node (ref "LED4") (pin "2") (pinfunction "K_2") (pintype "input"))
      (node (ref "R30") (pin "2") (pinfunction "2_2") (pintype "input"))
    )
    (net (code "32") (name "Net-(LED4-K-Pad4)") (class "Default")
      (node (ref "LED4") (pin "4") (pinfunction "K_4") (pintype "input"))
      (node (ref "R29") (pin "2") (pinfunction "2_2") (pintype "input"))
    )
    (net (code "33") (name "Net-(Q1-B)") (class "Default")
      (node (ref "Q1") (pin "1") (pinfunction "B_1") (pintype "input"))
      (node (ref "R1") (pin "1") (pinfunction "1_1") (pintype "input"))
    )
    (net (code "34") (name "Net-(Q1-C)") (class "Default")
      (node (ref "Q1") (pin "3") (pinfunction "C_3") (pintype "input"))
      (node (ref "R2") (pin "2") (pinfunction "2_2") (pintype "input"))
    )
    (net (code "35") (name "Net-(R13-Pad2)") (class "Default")
      (node (ref "R13") (pin "2") (pinfunction "2_2") (pintype "input"))
      (node (ref "R37") (pin "1") (pinfunction "1_1") (pintype "input"))
    )
    (net (code "36") (name "Net-(U1-BOOT0)") (class "Default")
      (node (ref "R8") (pin "1") (pinfunction "1_1") (pintype "input"))
      (node (ref "U1") (pin "44") (pinfunction "BOOT0_44") (pintype "input"))
    )
    (net (code "37") (name "Net-(U1-PB12SPI2_NSSI2C2_SMBAUSART3_CKTIM1_BKIN)") (class "Default")
      (node (ref "R12") (pin "1") (pinfunction "1_1") (pintype "input"))
      (node (ref "U1") (pin "25") (pinfunction "PB12SPI2_NSSI2C2_SMBAUSART3_CKTIM1_BKIN_25") (pintype "input"))
    )
    (net (code "38") (name "Net-(USB1-CC1)") (class "Default")
      (node (ref "R6") (pin "2") (pinfunction "2_2") (pintype "input"))
      (node (ref "USB1") (pin "A5") (pinfunction "CC1_A5") (pintype "input"))
    )
    (net (code "39") (name "Net-(USB1-CC2)") (class "Default")
      (node (ref "R4") (pin "1") (pinfunction "1_1") (pintype "input"))
      (node (ref "USB1") (pin "B5") (pinfunction "CC2_B5") (pintype "input"))
    )
    (net (code "40") (name "PA0{slash}ADC_IN0") (class "Default")
      (node (ref "H10") (pin "14") (pinfunction "14_14") (pintype "input"))
      (node (ref "H11") (pin "14") (pinfunction "14_14") (pintype "input"))
      (node (ref "MCU1") (pin "14") (pinfunction "PA0/TIM1_CH1N/UART3_TX/TIM8_CH1/LCD23/ADC_IN0/CMP1_P/OPA1_P/CMP0_P1_14") (pintype "input"))
      (node (ref "R37") (pin "2") (pinfunction "2_2") (pintype "input"))
    )
    (net (code "41") (name "PA1{slash}USER_KEY") (class "Default")
      (node (ref "C15") (pin "2") (pinfunction "2_2") (pintype "input"))
      (node (ref "H10") (pin "15") (pinfunction "15_15") (pintype "input"))
      (node (ref "H11") (pin "15") (pinfunction "15_15") (pintype "input"))
      (node (ref "MCU1") (pin "15") (pinfunction "PA1/TIM1_CH2N/TIM5_CH1N/UART3_RX/TIM8_CH2/LCD22/ADC_IN1/CMP1_N/OPA1_N/CMP0_P2_15") (pintype "input"))
      (node (ref "USER_KEY") (pin "1") (pinfunction "A_1") (pintype "input"))
      (node (ref "USER_KEY") (pin "2") (pinfunction "B_2") (pintype "input"))
    )
    (net (code "42") (name "PA2{slash}DEMO_UART0_TX") (class "Default")
      (node (ref "H10") (pin "16") (pinfunction "16_16") (pintype "input"))
      (node (ref "H11") (pin "16") (pinfunction "16_16") (pintype "input"))
      (node (ref "H9") (pin "4") (pinfunction "4_4") (pintype "input"))
      (node (ref "MCU1") (pin "16") (pinfunction "PA2/TIM1_CH3N/TIM5_CH1/UART0_TX/UART1_TX/TIM8_CH3/LCD21/ADC_IN2/OPA1_OUT_16") (pintype "input"))
    )
    (net (code "43") (name "PA3{slash}DEMO_UART0_RX") (class "Default")
      (node (ref "H2") (pin "1") (pinfunction "1_1") (pintype "input"))
      (node (ref "H5") (pin "1") (pinfunction "1_1") (pintype "input"))
      (node (ref "H9") (pin "5") (pinfunction "5_5") (pintype "input"))
      (node (ref "MCU1") (pin "17") (pinfunction "PA3/TIM1_CH4N/UART0_RX/UART1_RX/TIM8_CH4/LCD20/ADC_IN3/OPA0_P/CMP2_P1_17") (pintype "input"))
    )
    (net (code "44") (name "PA4{slash}SPI0_CS") (class "Default")
      (node (ref "H2") (pin "4") (pinfunction "4_4") (pintype "input"))
      (node (ref "H5") (pin "4") (pinfunction "4_4") (pintype "input"))
      (node (ref "MCU1") (pin "20") (pinfunction "PA4/UART5_TX/SPI0_CS/UART0_TX/UART1_TX/LCD19/ADC_IN14/OPA0_N/CMP2_P2_20") (pintype "input"))
      (node (ref "U15") (pin "1") (pinfunction "CS#_1") (pintype "input"))
    )
    (net (code "45") (name "PA5{slash}SPI0_SCK") (class "Default")
      (node (ref "H2") (pin "5") (pinfunction "5_5") (pintype "input"))
      (node (ref "H5") (pin "5") (pinfunction "5_5") (pintype "input"))
      (node (ref "MCU1") (pin "21") (pinfunction "PA5/UART5_RX/SPI0_SCK/UART0_RX/UART1_RX/TIM8_ETR/LCD18/ADC_IN5/OPA0_OUT_21") (pintype "input"))
      (node (ref "U15") (pin "6") (pinfunction "SCLK_6") (pintype "input"))
    )
    (net (code "46") (name "PA6{slash}SPI0_MISO") (class "Default")
      (node (ref "H2") (pin "6") (pinfunction "6_6") (pintype "input"))
      (node (ref "H5") (pin "6") (pinfunction "6_6") (pintype "input"))
      (node (ref "MCU1") (pin "22") (pinfunction "PA6/SPI0_MISO/TIM8_CH1/TIM1_BKIN/TIM6_CH1/LCD17/ADC_IN6_22") (pintype "input"))
      (node (ref "U15") (pin "2") (pinfunction "SO_2") (pintype "input"))
    )
    (net (code "47") (name "PA7{slash}SPI0_MOSI") (class "Default")
      (node (ref "H2") (pin "7") (pinfunction "7_7") (pintype "input"))
      (node (ref "H5") (pin "7") (pinfunction "7_7") (pintype "input"))
      (node (ref "MCU1") (pin "23") (pinfunction "PA7/ADC_ETR/SPI0_MOSI/TIM1_CH1/TIM8_CH2/TIM1_CH1N/TIM7_CH1/LCD16/ADC_IN7_23") (pintype "input"))
      (node (ref "U15") (pin "5") (pinfunction "SI_5") (pintype "input"))
    )
    (net (code "48") (name "PA8{slash}LCD0") (class "Default")
      (node (ref "H1") (pin "1") (pinfunction "1_1") (pintype "input"))
      (node (ref "H6") (pin "8") (pinfunction "8_8") (pintype "input"))
      (node (ref "H7") (pin "8") (pinfunction "8_8") (pintype "input"))
      (node (ref "MCU1") (pin "41") (pinfunction "PA8/MCO/TIM1_CH1/CMP2_OUT/LCD0_41") (pintype "input"))
    )
    (net (code "49") (name "PA9") (class "Default")
      (node (ref "H6") (pin "7") (pinfunction "7_7") (pintype "input"))
      (node (ref "H7") (pin "7") (pinfunction "7_7") (pintype "input"))
      (node (ref "MCU1") (pin "42") (pinfunction "PA9/MCO/I2C1_SCL/UART0_TX/UART1_TX/TIM1_CH2/TIM5_BKIN/CMP0_OUT/LCD40_42") (pintype "input"))
    )
    (net (code "50") (name "PA10{slash}I2C1_SDA") (class "Default")
      (node (ref "H6") (pin "6") (pinfunction "6_6") (pintype "input"))
      (node (ref "H7") (pin "6") (pinfunction "6_6") (pintype "input"))
      (node (ref "MCU1") (pin "43") (pinfunction "PA10/I2C1_SDA/UART0_RX/UART1_RX/TIM1_CH3/TIM7_BKIN/CMP1_OUT/LCD41/CMP0_P0_43") (pintype "input"))
      (node (ref "R25") (pin "1") (pinfunction "1_1") (pintype "input"))
      (node (ref "U12") (pin "5") (pinfunction "SDA_5") (pintype "input"))
    )
    (net (code "51") (name "PA11{slash}I2C1_SCL") (class "Default")
      (node (ref "H6") (pin "5") (pinfunction "5_5") (pintype "input"))
      (node (ref "H7") (pin "5") (pinfunction "5_5") (pintype "input"))
      (node (ref "MCU1") (pin "44") (pinfunction "PA11/I2C0_SCL/I2C1_SCL/CAN_RX/TIM1_CH4/LCD42/ADC_IN16/CMP3_P2_44") (pintype "input"))
      (node (ref "R24") (pin "1") (pinfunction "1_1") (pintype "input"))
      (node (ref "U12") (pin "6") (pinfunction "SCL_6") (pintype "input"))
    )
    (net (code "52") (name "PA12{slash}CMP3_N") (class "Default")
      (node (ref "H6") (pin "4") (pinfunction "4_4") (pintype "input"))
      (node (ref "H7") (pin "4") (pinfunction "4_4") (pintype "input"))
      (node (ref "MCU1") (pin "45") (pinfunction "PA12/I2C0_SDA/I2C1_SDA/TIM1_ETR/CAN_TX/TIM1_CH4N/LCD43/ADC_IN17/CMP3_N_45") (pintype "input"))
    )
    (net (code "53") (name "PA13{slash}DEMO_SWDIO") (class "Default")
      (node (ref "H6") (pin "3") (pinfunction "3_3") (pintype "input"))
      (node (ref "H7") (pin "3") (pinfunction "3_3") (pintype "input"))
      (node (ref "H9") (pin "6") (pinfunction "6_6") (pintype "input"))
      (node (ref "MCU1") (pin "46") (pinfunction "PA13/SWDIO/UART1_RX/UART0_RX_46") (pintype "input"))
    )
    (net (code "54") (name "PA14{slash}DEMO_SWCLK") (class "Default")
      (node (ref "H12") (pin "16") (pinfunction "16_16") (pintype "input"))
      (node (ref "H13") (pin "16") (pinfunction "16_16") (pintype "input"))
      (node (ref "H9") (pin "7") (pinfunction "7_7") (pintype "input"))
      (node (ref "MCU1") (pin "49") (pinfunction "PA14/SWCLK/UART0_TX/UART1_TX_49") (pintype "input"))
    )
    (net (code "55") (name "PA15") (class "Default")
      (node (ref "H12") (pin "15") (pinfunction "15_15") (pintype "input"))
      (node (ref "H13") (pin "15") (pinfunction "15_15") (pintype "input"))
      (node (ref "MCU1") (pin "50") (pinfunction "PA15/SPI1_CS/UART0_RX/UART1_RX/TIM8_ETR/CMP0_P5_50") (pintype "input"))
    )
    (net (code "56") (name "PB0") (class "Default")
      (node (ref "H2") (pin "10") (pinfunction "10_10") (pintype "input"))
      (node (ref "H5") (pin "10") (pinfunction "10_10") (pintype "input"))
      (node (ref "MCU1") (pin "26") (pinfunction "PB0/TIM8_CH3/TIM1_CH2N/LCD13/ADC_IN12_26") (pintype "input"))
    )
    (net (code "57") (name "PB1") (class "Default")
      (node (ref "H2") (pin "11") (pinfunction "11_11") (pintype "input"))
      (node (ref "H5") (pin "11") (pinfunction "11_11") (pintype "input"))
      (node (ref "MCU1") (pin "27") (pinfunction "PB1/TIM1_CH3/TIM8_CH4/TIM1_CH3N/LCD12/ADC_IN8_27") (pintype "input"))
    )
    (net (code "58") (name "PB2{slash}BEEP") (class "Default")
      (node (ref "BUZZER1") (pin "2") (pinfunction "2_2") (pintype "input"))
      (node (ref "C22") (pin "1") (pinfunction "1_1") (pintype "input"))
      (node (ref "D2") (pin "2") (pinfunction "A_2") (pintype "input"))
      (node (ref "H12") (pin "5") (pinfunction "5_5") (pintype "input"))
      (node (ref "H13") (pin "5") (pinfunction "5_5") (pintype "input"))
      (node (ref "MCU1") (pin "60") (pinfunction "PB2/MCO/BEEP/TIM1_ETR/CMP1_OUT/LCD30/ADC_IN9_60") (pintype "input"))
    )
    (net (code "59") (name "PB3{slash}LCD35") (class "Default")
      (node (ref "C18") (pin "2") (pinfunction "2_2") (pintype "input"))
      (node (ref "H12") (pin "10") (pinfunction "10_10") (pintype "input"))
      (node (ref "H13") (pin "10") (pinfunction "10_10") (pintype "input"))
      (node (ref "MCU1") (pin "55") (pinfunction "PB3/UART4_TX/SPI1_SCK/TIM8_CH2/TIM1_BKIN/LCD35/ADC_IN10/CMP0_N_55") (pintype "input"))
    )
    (net (code "60") (name "PB4{slash}LCD34") (class "Default")
      (node (ref "C18") (pin "1") (pinfunction "1_1") (pintype "input"))
      (node (ref "H12") (pin "9") (pinfunction "9_9") (pintype "input"))
      (node (ref "H13") (pin "9") (pinfunction "9_9") (pintype "input"))
      (node (ref "MCU1") (pin "56") (pinfunction "PB4/UART4_RX/SPI1_MISO/TIM8_CH1/TIM1_CH1/TIM7_BKIN/CMP0_OUT/LCD34/ADC_IN11_56") (pintype "input"))
    )
    (net (code "61") (name "PB5{slash}LCD33") (class "Default")
      (node (ref "C19") (pin "1") (pinfunction "1_1") (pintype "input"))
      (node (ref "H12") (pin "8") (pinfunction "8_8") (pintype "input"))
      (node (ref "H13") (pin "8") (pinfunction "8_8") (pintype "input"))
      (node (ref "MCU1") (pin "57") (pinfunction "PB5/SPI1_MISO/TIM8_CH2/TIM1_CH2/TIM6_BKIN/LCD33/ADC_IN13/CMP2_P0_57") (pintype "input"))
    )
    (net (code "62") (name "PB6{slash}LCD32") (class "Default")
      (node (ref "C20") (pin "1") (pinfunction "1_1") (pintype "input"))
      (node (ref "H12") (pin "7") (pinfunction "7_7") (pintype "input"))
      (node (ref "H13") (pin "7") (pinfunction "7_7") (pintype "input"))
      (node (ref "MCU1") (pin "58") (pinfunction "PB6/I2C0_SCL/I2C1_SCL/UART0_TX/UART1_TX/TIM1_CH3/TIM6_CH1N/LCD32/ADC_IN14/CMP2_N_58") (pintype "input"))
    )
    (net (code "63") (name "PB7") (class "Default")
      (node (ref "H12") (pin "6") (pinfunction "6_6") (pintype "input"))
      (node (ref "H13") (pin "6") (pinfunction "6_6") (pintype "input"))
      (node (ref "MCU1") (pin "59") (pinfunction "PB7/I2C0_SDA/I2C1_SDA/UART0_RX/UART1_RX/TIM1_CH4/TIM7_CH1N//CMP2_OUT/LCD32/ADC_IN15_59") (pintype "input"))
    )
    (net (code "64") (name "PB8{slash}CAN_RX") (class "Default")
      (node (ref "H12") (pin "4") (pinfunction "4_4") (pintype "input"))
      (node (ref "H13") (pin "4") (pinfunction "4_4") (pintype "input"))
      (node (ref "MCU1") (pin "61") (pinfunction "PB8/I2C0_SCL/CAN_RX/TIM6_CH1/LCD29/CMP2_P3_61") (pintype "input"))
      (node (ref "U14") (pin "4") (pinfunction "RXD_4") (pintype "input"))
    )
    (net (code "65") (name "PB9{slash}CAN_TX") (class "Default")
      (node (ref "H12") (pin "3") (pinfunction "3_3") (pintype "input"))
      (node (ref "H13") (pin "3") (pinfunction "3_3") (pintype "input"))
      (node (ref "MCU1") (pin "62") (pinfunction "PB9/I2C0_SDA/SPI1_CS/CAN_TX/TIM7_CH1/LCD28/CMP2_P4_62") (pintype "input"))
      (node (ref "U14") (pin "1") (pinfunction "TXD_1") (pintype "input"))
    )
    (net (code "66") (name "PB10{slash}LCD10") (class "Default")
      (node (ref "H1") (pin "11") (pinfunction "11_11") (pintype "input"))
      (node (ref "H2") (pin "13") (pinfunction "13_13") (pintype "input"))
      (node (ref "H5") (pin "13") (pinfunction "13_13") (pintype "input"))
      (node (ref "MCU1") (pin "29") (pinfunction "PB10/I2C0_SCL/I2C1_SCL/UART2_TX/SPI1_SCK/TIM8_CH3/TIM6_CH1/LCD10/CMP0_P3_29") (pintype "input"))
    )
    (net (code "67") (name "PB11{slash}LCD9") (class "Default")
      (node (ref "H1") (pin "10") (pinfunction "10_10") (pintype "input"))
      (node (ref "H2") (pin "14") (pinfunction "14_14") (pintype "input"))
      (node (ref "H5") (pin "14") (pinfunction "14_14") (pintype "input"))
      (node (ref "MCU1") (pin "30") (pinfunction "PB11/I2C0_SDA/I2C1_SDA/UART2_RX/TIM8_CH4/TIM7_CH1/LCD9/CMP0_P4_30") (pintype "input"))
    )
    (net (code "68") (name "PB12{slash}LCD8") (class "Default")
      (node (ref "H1") (pin "9") (pinfunction "9_9") (pintype "input"))
      (node (ref "H6") (pin "16") (pinfunction "16_16") (pintype "input"))
      (node (ref "H7") (pin "16") (pinfunction "16_16") (pintype "input"))
      (node (ref "MCU1") (pin "33") (pinfunction "PB12/SPI0_CS/SPI1_CS/TIM1_BKIN/TIM5_BKIN/LCD8_33") (pintype "input"))
    )
    (net (code "69") (name "PB13{slash}LCD7") (class "Default")
      (node (ref "H1") (pin "8") (pinfunction "8_8") (pintype "input"))
      (node (ref "H6") (pin "15") (pinfunction "15_15") (pintype "input"))
      (node (ref "H7") (pin "15") (pinfunction "15_15") (pintype "input"))
      (node (ref "MCU1") (pin "34") (pinfunction "PB13/I2C1_SDA/SPI0_SCK/SPI1_SCK/TIM1_CH1N/LCD7_34") (pintype "input"))
    )
    (net (code "70") (name "PB14{slash}LCD6") (class "Default")
      (node (ref "H1") (pin "7") (pinfunction "7_7") (pintype "input"))
      (node (ref "H6") (pin "14") (pinfunction "14_14") (pintype "input"))
      (node (ref "H7") (pin "14") (pinfunction "14_14") (pintype "input"))
      (node (ref "MCU1") (pin "35") (pinfunction "PB14/SPI0_MISO/SPI1_MISO/TIM1_CH2N/TIM5_CH1/LCD6_35") (pintype "input"))
    )
    (net (code "71") (name "PB15{slash}LCD5") (class "Default")
      (node (ref "H1") (pin "6") (pinfunction "6_6") (pintype "input"))
      (node (ref "H6") (pin "13") (pinfunction "13_13") (pintype "input"))
      (node (ref "H7") (pin "13") (pinfunction "13_13") (pintype "input"))
      (node (ref "MCU1") (pin "36") (pinfunction "PB15/SPI0_MOSI/SPI1_MOSI/TIM1_CH3N/TIM5_CH1N/LCD5_36") (pintype "input"))
    )
    (net (code "72") (name "PC0{slash}OPA3_P") (class "Default")
      (node (ref "H10") (pin "8") (pinfunction "8_8") (pintype "input"))
      (node (ref "H11") (pin "8") (pinfunction "8_8") (pintype "input"))
      (node (ref "MCU1") (pin "8") (pinfunction "PC0/UART5_TX/LCD27/ADC_IN18/OPA3_P_8") (pintype "input"))
    )
    (net (code "73") (name "PC1{slash}OPA3_N") (class "Default")
      (node (ref "H10") (pin "9") (pinfunction "9_9") (pintype "input"))
      (node (ref "H11") (pin "9") (pinfunction "9_9") (pintype "input"))
      (node (ref "MCU1") (pin "9") (pinfunction "PC1/UART5_RX/LCD26/ADC_IN19/OPA3_N_9") (pintype "input"))
      (node (ref "R33") (pin "2") (pinfunction "2_2") (pintype "input"))
      (node (ref "R34") (pin "1") (pinfunction "1_1") (pintype "input"))
    )
    (net (code "74") (name "PC2{slash}OPA3_OUT") (class "Default")
      (node (ref "H10") (pin "10") (pinfunction "10_10") (pintype "input"))
      (node (ref "H11") (pin "10") (pinfunction "10_10") (pintype "input"))
      (node (ref "MCU1") (pin "10") (pinfunction "PC2/SPI1_MISO/LCD25/ADC_IN20/OPA3_OUT_10") (pintype "input"))
      (node (ref "R34") (pin "2") (pinfunction "2_2") (pintype "input"))
    )
    (net (code "75") (name "PC3") (class "Default")
      (node (ref "H10") (pin "11") (pinfunction "11_11") (pintype "input"))
      (node (ref "H11") (pin "11") (pinfunction "11_11") (pintype "input"))
      (node (ref "MCU1") (pin "11") (pinfunction "PC3/SPI1_MOSI/LCD24/ADC_IN21_11") (pintype "input"))
    )
    (net (code "76") (name "PC4{slash}CMP3_P0") (class "Default")
      (node (ref "H2") (pin "8") (pinfunction "8_8") (pintype "input"))
      (node (ref "H5") (pin "8") (pinfunction "8_8") (pintype "input"))
      (node (ref "MCU1") (pin "24") (pinfunction "PC4/UART2_TX/LCD15/ADC_IN22/CMP3_P0_24") (pintype "input"))
    )
    (net (code "77") (name "PC5") (class "Default")
      (node (ref "H2") (pin "9") (pinfunction "9_9") (pintype "input"))
      (node (ref "H5") (pin "9") (pinfunction "9_9") (pintype "input"))
      (node (ref "MCU1") (pin "25") (pinfunction "PC5/UART2_RX/LCD14/ADC_IN23/CMP3_P1_25") (pintype "input"))
    )
    (net (code "78") (name "PC6{slash}LCD4") (class "Default")
      (node (ref "H1") (pin "5") (pinfunction "5_5") (pintype "input"))
      (node (ref "H6") (pin "12") (pinfunction "12_12") (pintype "input"))
      (node (ref "H7") (pin "12") (pinfunction "12_12") (pintype "input"))
      (node (ref "MCU1") (pin "37") (pinfunction "PC6/TIM8_CH1/LCD4_37") (pintype "input"))
    )
    (net (code "79") (name "PC7{slash}LCD3") (class "Default")
      (node (ref "H1") (pin "4") (pinfunction "4_4") (pintype "input"))
      (node (ref "H6") (pin "11") (pinfunction "11_11") (pintype "input"))
      (node (ref "H7") (pin "11") (pinfunction "11_11") (pintype "input"))
      (node (ref "MCU1") (pin "38") (pinfunction "PC7/TIM8_CH2/LCD3_38") (pintype "input"))
    )
    (net (code "80") (name "PC8{slash}LCD2") (class "Default")
      (node (ref "H1") (pin "3") (pinfunction "3_3") (pintype "input"))
      (node (ref "H6") (pin "10") (pinfunction "10_10") (pintype "input"))
      (node (ref "H7") (pin "10") (pinfunction "10_10") (pintype "input"))
      (node (ref "MCU1") (pin "39") (pinfunction "PC8/TIM8_CH3/LCD2_39") (pintype "input"))
    )
    (net (code "81") (name "PC9{slash}LCD1") (class "Default")
      (node (ref "H1") (pin "2") (pinfunction "2_2") (pintype "input"))
      (node (ref "H6") (pin "9") (pinfunction "9_9") (pintype "input"))
      (node (ref "H7") (pin "9") (pinfunction "9_9") (pintype "input"))
      (node (ref "MCU1") (pin "40") (pinfunction "PC9/TIM8_CH4/LCD1_40") (pintype "input"))
    )
    (net (code "82") (name "PC10{slash}LED_B") (class "Default")
      (node (ref "H12") (pin "14") (pinfunction "14_14") (pintype "input"))
      (node (ref "H13") (pin "14") (pinfunction "14_14") (pintype "input"))
      (node (ref "MCU1") (pin "51") (pinfunction "PC10/UART2_TX/UART3_TX/LCD39/CMP_P3/OPA2_P_51") (pintype "input"))
      (node (ref "R30") (pin "1") (pinfunction "1_1") (pintype "input"))
    )
    (net (code "83") (name "PC11{slash}LED_G") (class "Default")
      (node (ref "H12") (pin "13") (pinfunction "13_13") (pintype "input"))
      (node (ref "H13") (pin "13") (pinfunction "13_13") (pintype "input"))
      (node (ref "MCU1") (pin "52") (pinfunction "PC11/UART2_RX/UART3_RX/LCD38/CMP_P4/OPA2_N_52") (pintype "input"))
      (node (ref "R29") (pin "1") (pinfunction "1_1") (pintype "input"))
    )
    (net (code "84") (name "PC12{slash}LED_R") (class "Default")
      (node (ref "H12") (pin "12") (pinfunction "12_12") (pintype "input"))
      (node (ref "H13") (pin "12") (pinfunction "12_12") (pintype "input"))
      (node (ref "MCU1") (pin "53") (pinfunction "PC12/UART4_TX/LCD37/ADC_IN25/OPA2_OUT_53") (pintype "input"))
      (node (ref "R31") (pin "1") (pinfunction "1_1") (pintype "input"))
    )
    (net (code "85") (name "PC13") (class "Default")
      (node (ref "H10") (pin "2") (pinfunction "2_2") (pintype "input"))
      (node (ref "H11") (pin "2") (pinfunction "2_2") (pintype "input"))
      (node (ref "MCU1") (pin "2") (pinfunction "PC13/RTC_BEACON_2") (pintype "input"))
    )
    (net (code "86") (name "PC14{slash}OSC32_IN") (class "Default")
      (node (ref "C24") (pin "1") (pinfunction "1_1") (pintype "input"))
      (node (ref "H10") (pin "3") (pinfunction "3_3") (pintype "input"))
      (node (ref "H11") (pin "3") (pinfunction "3_3") (pintype "input"))
      (node (ref "MCU1") (pin "3") (pinfunction "PC14/OSC32_IN_3") (pintype "input"))
      (node (ref "X3") (pin "1") (pinfunction "OSC1_1") (pintype "input"))
    )
    (net (code "87") (name "PC15{slash}OSC32_OUT") (class "Default")
      (node (ref "C25") (pin "1") (pinfunction "1_1") (pintype "input"))
      (node (ref "H10") (pin "4") (pinfunction "4_4") (pintype "input"))
      (node (ref "H11") (pin "4") (pinfunction "4_4") (pintype "input"))
      (node (ref "MCU1") (pin "4") (pinfunction "PC15/OSC32_OUT_4") (pintype "input"))
      (node (ref "X3") (pin "2") (pinfunction "OSC2_2") (pintype "input"))
    )
    (net (code "88") (name "PER_3V3") (class "Default")
      (node (ref "BUZZER1") (pin "1") (pinfunction "1_1") (pintype "input"))
      (node (ref "C13") (pin "1") (pinfunction "1_1") (pintype "input"))
      (node (ref "C16") (pin "1") (pinfunction "1_1") (pintype "input"))
      (node (ref "C21") (pin "2") (pinfunction "2_2") (pintype "input"))
      (node (ref "C22") (pin "2") (pinfunction "2_2") (pintype "input"))
      (node (ref "D2") (pin "1") (pinfunction "C_1") (pintype "input"))
      (node (ref "H3") (pin "4") (pinfunction "4_4") (pintype "input"))
      (node (ref "LED4") (pin "3") (pinfunction "A_3") (pintype "input"))
      (node (ref "R24") (pin "2") (pinfunction "2_2") (pintype "input"))
      (node (ref "R25") (pin "2") (pinfunction "2_2") (pintype "input"))
      (node (ref "R37") (pin "3") (pinfunction "3_3") (pintype "input"))
      (node (ref "U12") (pin "8") (pinfunction "VCC_8") (pintype "input"))
      (node (ref "U14") (pin "3") (pinfunction "VCC_3") (pintype "input"))
      (node (ref "U15") (pin "3") (pinfunction "WP#_3") (pintype "input"))
      (node (ref "U15") (pin "8") (pinfunction "Vcc_8") (pintype "input"))
    )
    (net (code "89") (name "PF0{slash}OSC_IN") (class "Default")
      (node (ref "C12") (pin "1") (pinfunction "1_1") (pintype "input"))
      (node (ref "H10") (pin "5") (pinfunction "5_5") (pintype "input"))
      (node (ref "H11") (pin "5") (pinfunction "5_5") (pintype "input"))
      (node (ref "MCU1") (pin "5") (pinfunction "PF0/I2C0_SDA/I2C1_SDA/OSC_IN_5") (pintype "input"))
      (node (ref "X2") (pin "3") (pinfunction "OSC2_3") (pintype "input"))
    )
    (net (code "90") (name "PF1{slash}OSC_OUT") (class "Default")
      (node (ref "C23") (pin "2") (pinfunction "2_2") (pintype "input"))
      (node (ref "H10") (pin "6") (pinfunction "6_6") (pintype "input"))
      (node (ref "H11") (pin "6") (pinfunction "6_6") (pintype "input"))
      (node (ref "MCU1") (pin "6") (pinfunction "PF1/I2C0_SCL/I2C1_SCL/OSC_OUT_6") (pintype "input"))
      (node (ref "X2") (pin "1") (pinfunction "OSC1_1") (pintype "input"))
    )
    (net (code "91") (name "PF2{slash}LCD11") (class "Default")
      (node (ref "H1") (pin "12") (pinfunction "12_12") (pintype "input"))
      (node (ref "H2") (pin "12") (pinfunction "12_12") (pintype "input"))
      (node (ref "H5") (pin "12") (pinfunction "12_12") (pintype "input"))
      (node (ref "MCU1") (pin "28") (pinfunction "PF2/TIM8_ETR/TIM5_CH1/LCD11_28") (pintype "input"))
    )
    (net (code "92") (name "PF3{slash}CMP3_OUT") (class "Default")
      (node (ref "H12") (pin "11") (pinfunction "11_11") (pintype "input"))
      (node (ref "H13") (pin "11") (pinfunction "11_11") (pintype "input"))
      (node (ref "MCU1") (pin "54") (pinfunction "PF3/UART4_RX/TIM8_ETR/CMP3_OUT/LCD36/ADC_IN24_54") (pintype "input"))
    )
    (net (code "93") (name "SEG0") (class "Default")
      (node (ref "H4") (pin "5") (pinfunction "5_5") (pintype "input"))
      (node (ref "LCD1") (pin "5") (pinfunction "5_5") (pintype "input"))
    )
    (net (code "94") (name "SEG1") (class "Default")
      (node (ref "H4") (pin "6") (pinfunction "6_6") (pintype "input"))
      (node (ref "LCD1") (pin "6") (pinfunction "6_6") (pintype "input"))
    )
    (net (code "95") (name "SEG2") (class "Default")
      (node (ref "H4") (pin "7") (pinfunction "7_7") (pintype "input"))
      (node (ref "LCD1") (pin "7") (pinfunction "7_7") (pintype "input"))
    )
    (net (code "96") (name "SEG3") (class "Default")
      (node (ref "H4") (pin "8") (pinfunction "8_8") (pintype "input"))
      (node (ref "LCD1") (pin "8") (pinfunction "8_8") (pintype "input"))
    )
    (net (code "97") (name "SEG4") (class "Default")
      (node (ref "H4") (pin "9") (pinfunction "9_9") (pintype "input"))
      (node (ref "LCD1") (pin "9") (pinfunction "9_9") (pintype "input"))
    )
    (net (code "98") (name "SEG5") (class "Default")
      (node (ref "H4") (pin "10") (pinfunction "10_10") (pintype "input"))
      (node (ref "LCD1") (pin "10") (pinfunction "10_10") (pintype "input"))
    )
    (net (code "99") (name "SEG6") (class "Default")
      (node (ref "H4") (pin "11") (pinfunction "11_11") (pintype "input"))
      (node (ref "LCD1") (pin "11") (pinfunction "11_11") (pintype "input"))
    )
    (net (code "100") (name "SEG7") (class "Default")
      (node (ref "H4") (pin "12") (pinfunction "12_12") (pintype "input"))
      (node (ref "LCD1") (pin "12") (pinfunction "12_12") (pintype "input"))
    )
    (net (code "101") (name "USB_DM") (class "Default")
      (node (ref "R3") (pin "2") (pinfunction "2_2") (pintype "input"))
      (node (ref "U1") (pin "32") (pinfunction "PA11USART1_CTSCAN_RXTIM1_CH4USBDM_32") (pintype "input"))
    )
    (net (code "102") (name "USB_DP") (class "Default")
      (node (ref "R5") (pin "2") (pinfunction "2_2") (pintype "input"))
      (node (ref "U1") (pin "33") (pinfunction "PA12USART1_RTSCAN_TXTIM1_ETRUSBDP_33") (pintype "input"))
    )
    (net (code "103") (name "USB_ENUM") (class "Default")
      (node (ref "R1") (pin "2") (pinfunction "2_2") (pintype "input"))
      (node (ref "U1") (pin "28") (pinfunction "PB15SPI2_MOSITIM1_CH3N_28") (pintype "input"))
    )
    (net (code "104") (name "VDD") (class "Default")
      (node (ref "C11") (pin "2") (pinfunction "2_2") (pintype "input"))
      (node (ref "H10") (pin "1") (pinfunction "1_1") (pintype "input"))
      (node (ref "H10") (pin "13") (pinfunction "13_13") (pintype "input"))
      (node (ref "H11") (pin "1") (pinfunction "1_1") (pintype "input"))
      (node (ref "H11") (pin "13") (pinfunction "13_13") (pintype "input"))
      (node (ref "H12") (pin "1") (pinfunction "1_1") (pintype "input"))
      (node (ref "H13") (pin "1") (pinfunction "1_1") (pintype "input"))
      (node (ref "H2") (pin "16") (pinfunction "16_16") (pintype "input"))
      (node (ref "H2") (pin "3") (pinfunction "3_3") (pintype "input"))
      (node (ref "H3") (pin "2") (pinfunction "2_2") (pintype "input"))
      (node (ref "H5") (pin "16") (pinfunction "16_16") (pintype "input"))
      (node (ref "H5") (pin "3") (pinfunction "3_3") (pintype "input"))
      (node (ref "H6") (pin "1") (pinfunction "1_1") (pintype "input"))
      (node (ref "H7") (pin "1") (pinfunction "1_1") (pintype "input"))
      (node (ref "MCU1") (pin "1") (pinfunction "VDD_1") (pintype "input"))
      (node (ref "MCU1") (pin "13") (pinfunction "VDDA_13") (pintype "input"))
      (node (ref "MCU1") (pin "19") (pinfunction "VDD_19") (pintype "input"))
      (node (ref "MCU1") (pin "32") (pinfunction "VDD_32") (pintype "input"))
      (node (ref "MCU1") (pin "48") (pinfunction "VDD_48") (pintype "input"))
      (node (ref "MCU1") (pin "64") (pinfunction "VDD_64") (pintype "input"))
    )
    (net (code "105") (name "unconnected-(U1-PA0_WKUPUSART2_CTSADC12_IN0TIM2_CH1_ETR-Pad10)") (class "Default")
      (node (ref "U1") (pin "10") (pinfunction "PA0_WKUPUSART2_CTSADC12_IN0TIM2_CH1_ETR_10") (pintype "input+no_connect"))
    )
    (net (code "106") (name "unconnected-(U1-PA1USART2_RTSADC12_IN1TIM2_CH2-Pad11)") (class "Default")
      (node (ref "U1") (pin "11") (pinfunction "PA1USART2_RTSADC12_IN1TIM2_CH2_11") (pintype "input+no_connect"))
    )
    (net (code "107") (name "unconnected-(U1-PA4SPI1_NSSUSART2_CKADC12_IN4-Pad14)") (class "Default")
      (node (ref "U1") (pin "14") (pinfunction "PA4SPI1_NSSUSART2_CKADC12_IN4_14") (pintype "input+no_connect"))
    )
    (net (code "108") (name "unconnected-(U1-PA5SPI1_SCKADC12_IN5-Pad15)") (class "Default")
      (node (ref "U1") (pin "15") (pinfunction "PA5SPI1_SCKADC12_IN5_15") (pintype "input+no_connect"))
    )
    (net (code "109") (name "unconnected-(U1-PA6SPI1_MISOADC12_IN6TIM3_CH1-Pad16)") (class "Default")
      (node (ref "U1") (pin "16") (pinfunction "PA6SPI1_MISOADC12_IN6TIM3_CH1_16") (pintype "input+no_connect"))
    )
    (net (code "110") (name "unconnected-(U1-PA7SPI1_MOSIADC12_IN7TIM3_CH2-Pad17)") (class "Default")
      (node (ref "U1") (pin "17") (pinfunction "PA7SPI1_MOSIADC12_IN7TIM3_CH2_17") (pintype "input+no_connect"))
    )
    (net (code "111") (name "unconnected-(U1-PA8USART1_CKTIM1_CH1MCO-Pad29)") (class "Default")
      (node (ref "U1") (pin "29") (pinfunction "PA8USART1_CKTIM1_CH1MCO_29") (pintype "input+no_connect"))
    )
    (net (code "112") (name "unconnected-(U1-PA9USART1_TXTIM1_CH2-Pad30)") (class "Default")
      (node (ref "U1") (pin "30") (pinfunction "PA9USART1_TXTIM1_CH2_30") (pintype "input+no_connect"))
    )
    (net (code "113") (name "unconnected-(U1-PA10USART1_RXTIM1_CH3-Pad31)") (class "Default")
      (node (ref "U1") (pin "31") (pinfunction "PA10USART1_RXTIM1_CH3_31") (pintype "input+no_connect"))
    )
    (net (code "114") (name "unconnected-(U1-PA15JTDI-Pad38)") (class "Default")
      (node (ref "U1") (pin "38") (pinfunction "PA15JTDI_38") (pintype "input+no_connect"))
    )
    (net (code "115") (name "unconnected-(U1-PB1ADC12_IN9TIM3_CH4-Pad19)") (class "Default")
      (node (ref "U1") (pin "19") (pinfunction "PB1ADC12_IN9TIM3_CH4_19") (pintype "input+no_connect"))
    )
    (net (code "116") (name "unconnected-(U1-PB2BOOT1-Pad20)") (class "Default")
      (node (ref "U1") (pin "20") (pinfunction "PB2BOOT1_20") (pintype "input+no_connect"))
    )
    (net (code "117") (name "unconnected-(U1-PB3JTDO-Pad39)") (class "Default")
      (node (ref "U1") (pin "39") (pinfunction "PB3JTDO_39") (pintype "input+no_connect"))
    )
    (net (code "118") (name "unconnected-(U1-PB4NJTRST-Pad40)") (class "Default")
      (node (ref "U1") (pin "40") (pinfunction "PB4NJTRST_40") (pintype "input+no_connect"))
    )
    (net (code "119") (name "unconnected-(U1-PB5I2C1_SMBA-Pad41)") (class "Default")
      (node (ref "U1") (pin "41") (pinfunction "PB5I2C1_SMBA_41") (pintype "input+no_connect"))
    )
    (net (code "120") (name "unconnected-(U1-PB6I2C1_SCLTIM4_CH1-Pad42)") (class "Default")
      (node (ref "U1") (pin "42") (pinfunction "PB6I2C1_SCLTIM4_CH1_42") (pintype "input+no_connect"))
    )
    (net (code "121") (name "unconnected-(U1-PB7I2C1_SDATIM4_CH2-Pad43)") (class "Default")
      (node (ref "U1") (pin "43") (pinfunction "PB7I2C1_SDATIM4_CH2_43") (pintype "input+no_connect"))
    )
    (net (code "122") (name "unconnected-(U1-PB8TIM4_CH3-Pad45)") (class "Default")
      (node (ref "U1") (pin "45") (pinfunction "PB8TIM4_CH3_45") (pintype "input+no_connect"))
    )
    (net (code "123") (name "unconnected-(U1-PB9TIM4_CH4-Pad46)") (class "Default")
      (node (ref "U1") (pin "46") (pinfunction "PB9TIM4_CH4_46") (pintype "input+no_connect"))
    )
    (net (code "124") (name "unconnected-(U1-PB10I2C2_SCLUSART3_TX-Pad21)") (class "Default")
      (node (ref "U1") (pin "21") (pinfunction "PB10I2C2_SCLUSART3_TX_21") (pintype "input+no_connect"))
    )
    (net (code "125") (name "unconnected-(U1-PB11I2C2_SDAUSART3_RX--Pad22)") (class "Default")
      (node (ref "U1") (pin "22") (pinfunction "PB11I2C2_SDAUSART3_RX-_22") (pintype "input+no_connect"))
    )
    (net (code "126") (name "unconnected-(U1-VBAT-Pad1)") (class "Default")
      (node (ref "U1") (pin "1") (pinfunction "VBAT_1") (pintype "input+no_connect"))
    )
    (net (code "127") (name "unconnected-(U3-IO-Pad3)") (class "Default")
      (node (ref "U3") (pin "3") (pinfunction "IO_3") (pintype "input"))
    )
    (net (code "128") (name "unconnected-(U3-IO-Pad4)") (class "Default")
      (node (ref "U3") (pin "4") (pinfunction "IO_4") (pintype "input"))
    )
    (net (code "129") (name "unconnected-(U14-NC-Pad5)") (class "Default")
      (node (ref "U14") (pin "5") (pinfunction "NC_5") (pintype "input+no_connect"))
    )
    (net (code "130") (name "unconnected-(U15-NC-Pad7)") (class "Default")
      (node (ref "U15") (pin "7") (pinfunction "NC_7") (pintype "input+no_connect"))
    )
    (net (code "131") (name "unconnected-(USB1-SBU1-PadA8)") (class "Default")
      (node (ref "USB1") (pin "A8") (pinfunction "SBU1_A8") (pintype "input+no_connect"))
    )
    (net (code "132") (name "unconnected-(USB1-SBU2-PadB8)") (class "Default")
      (node (ref "USB1") (pin "B8") (pinfunction "SBU2_B8") (pintype "input+no_connect"))
    )
  )
)
